# Sensor_Board.net
KiCad netlist of a schematic drawn in EAGLE
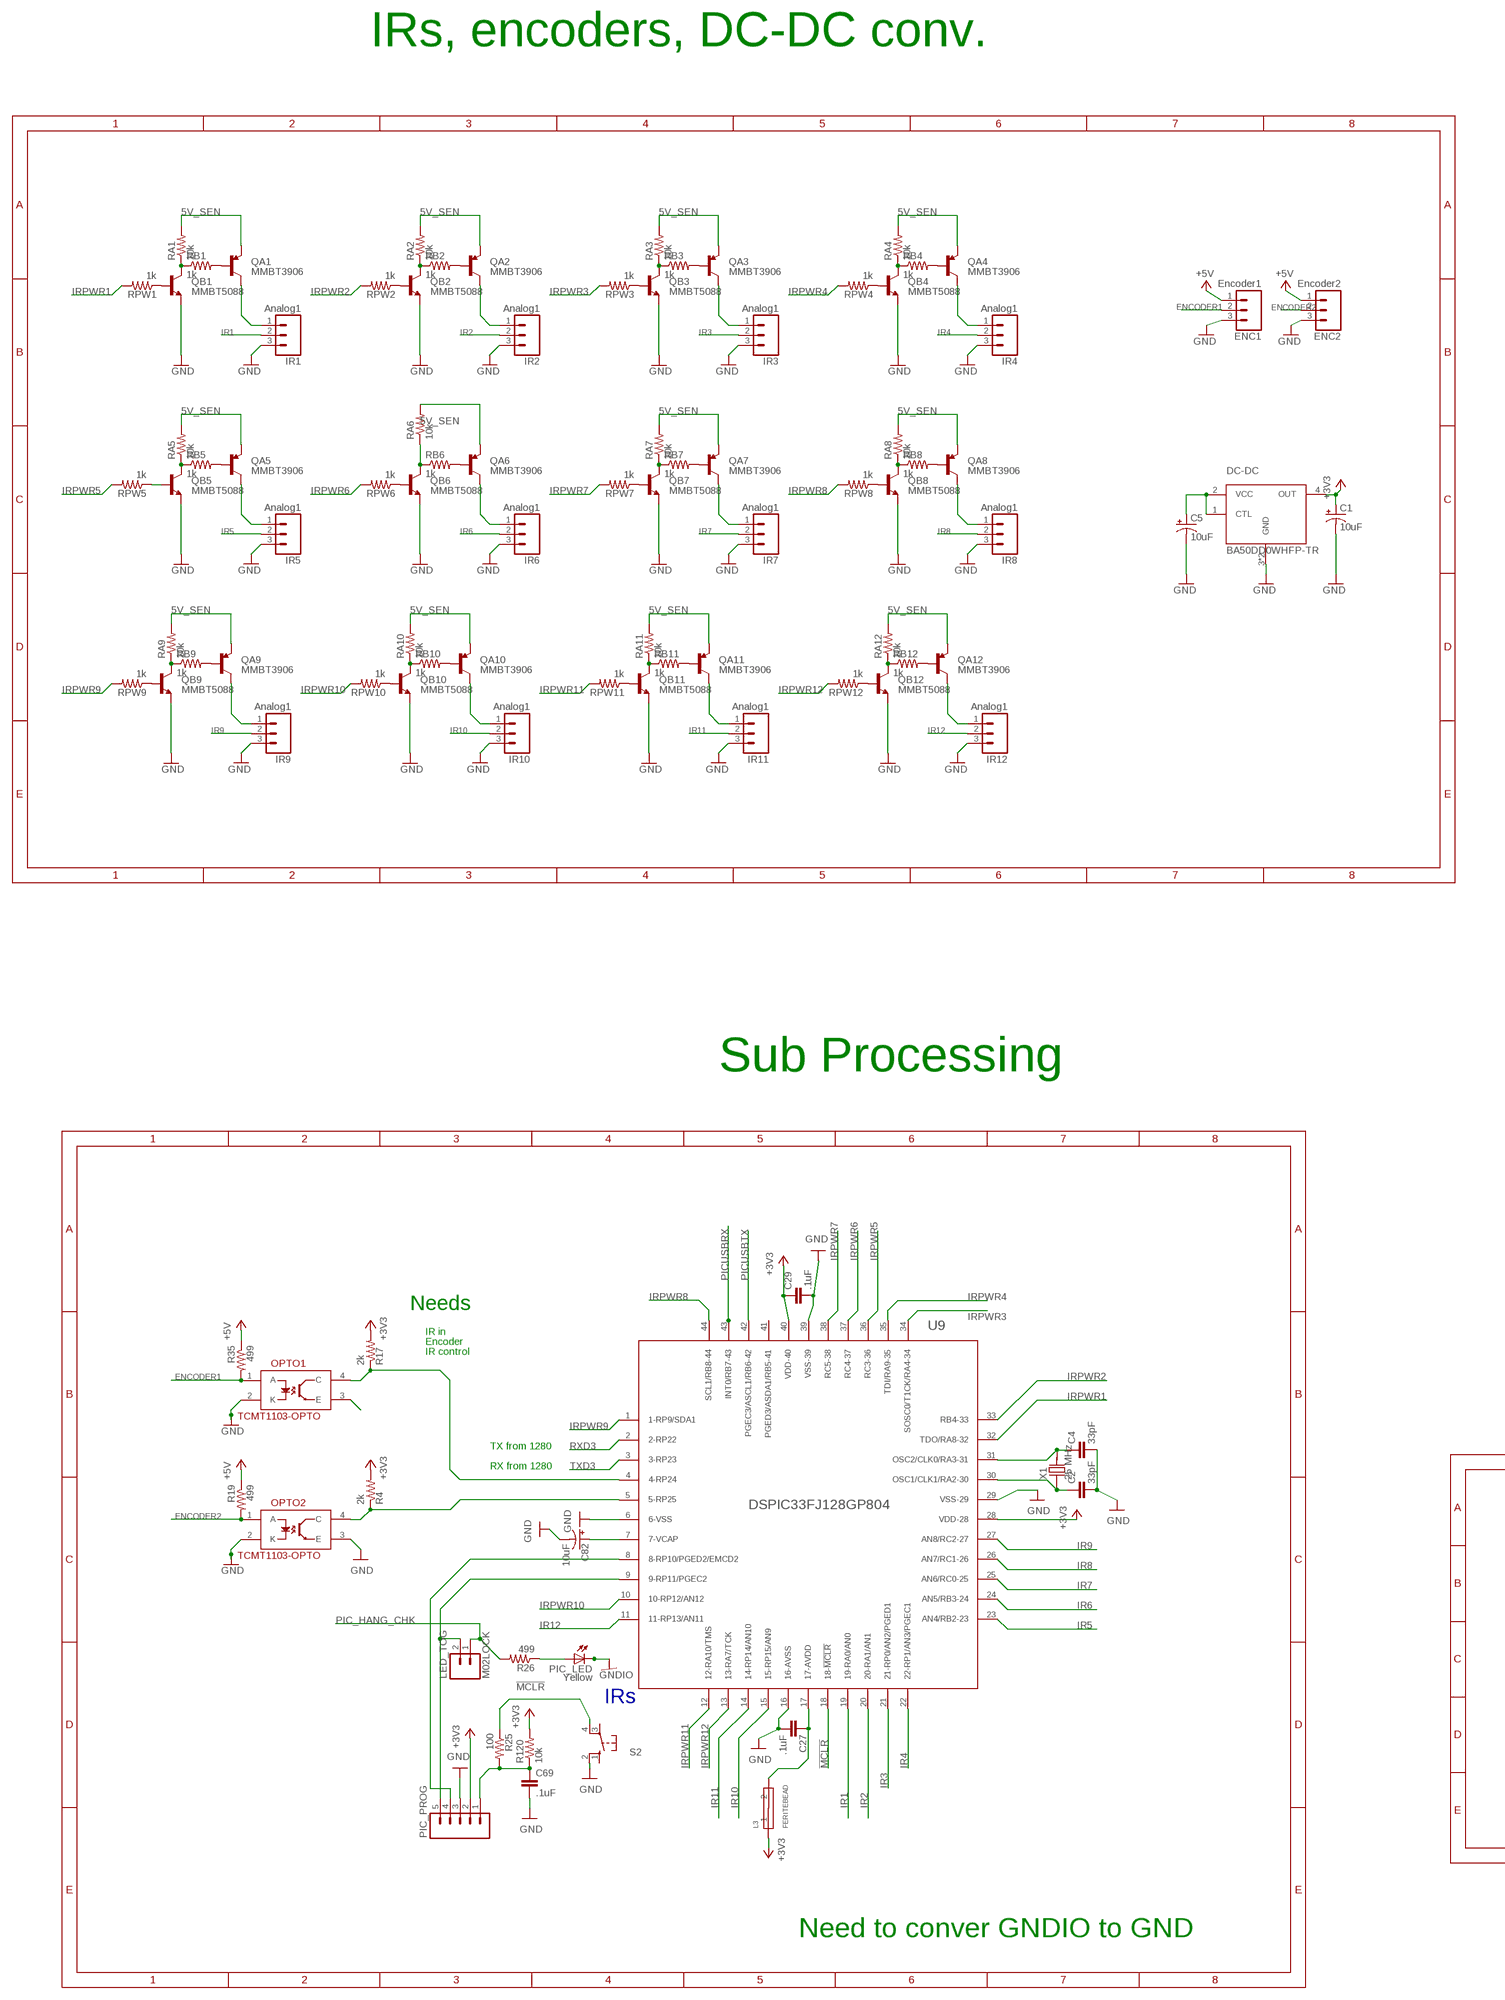
[diagram p0: schematic, sheet 1, part 1 of 3]
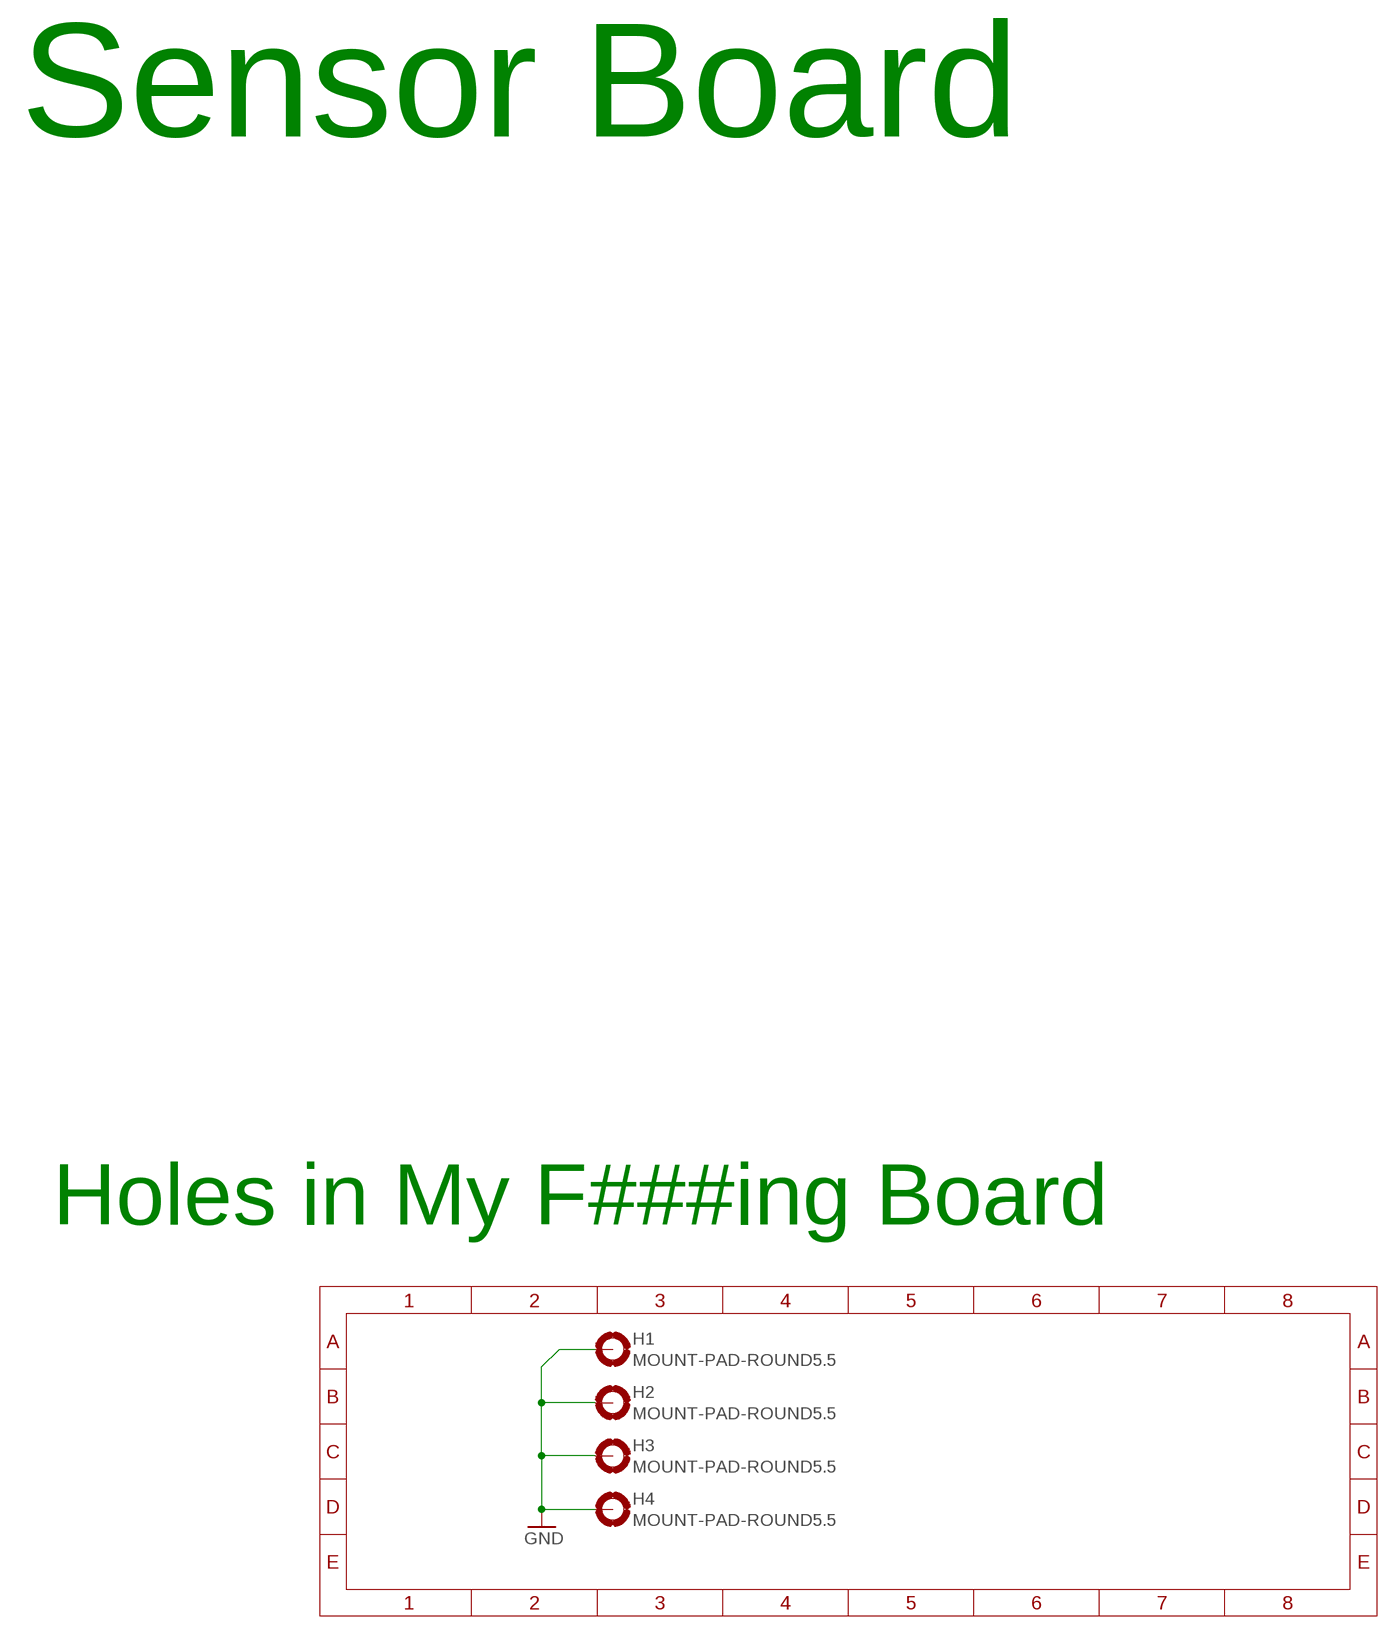
[diagram p1: schematic, sheet 1, part 2 of 3]
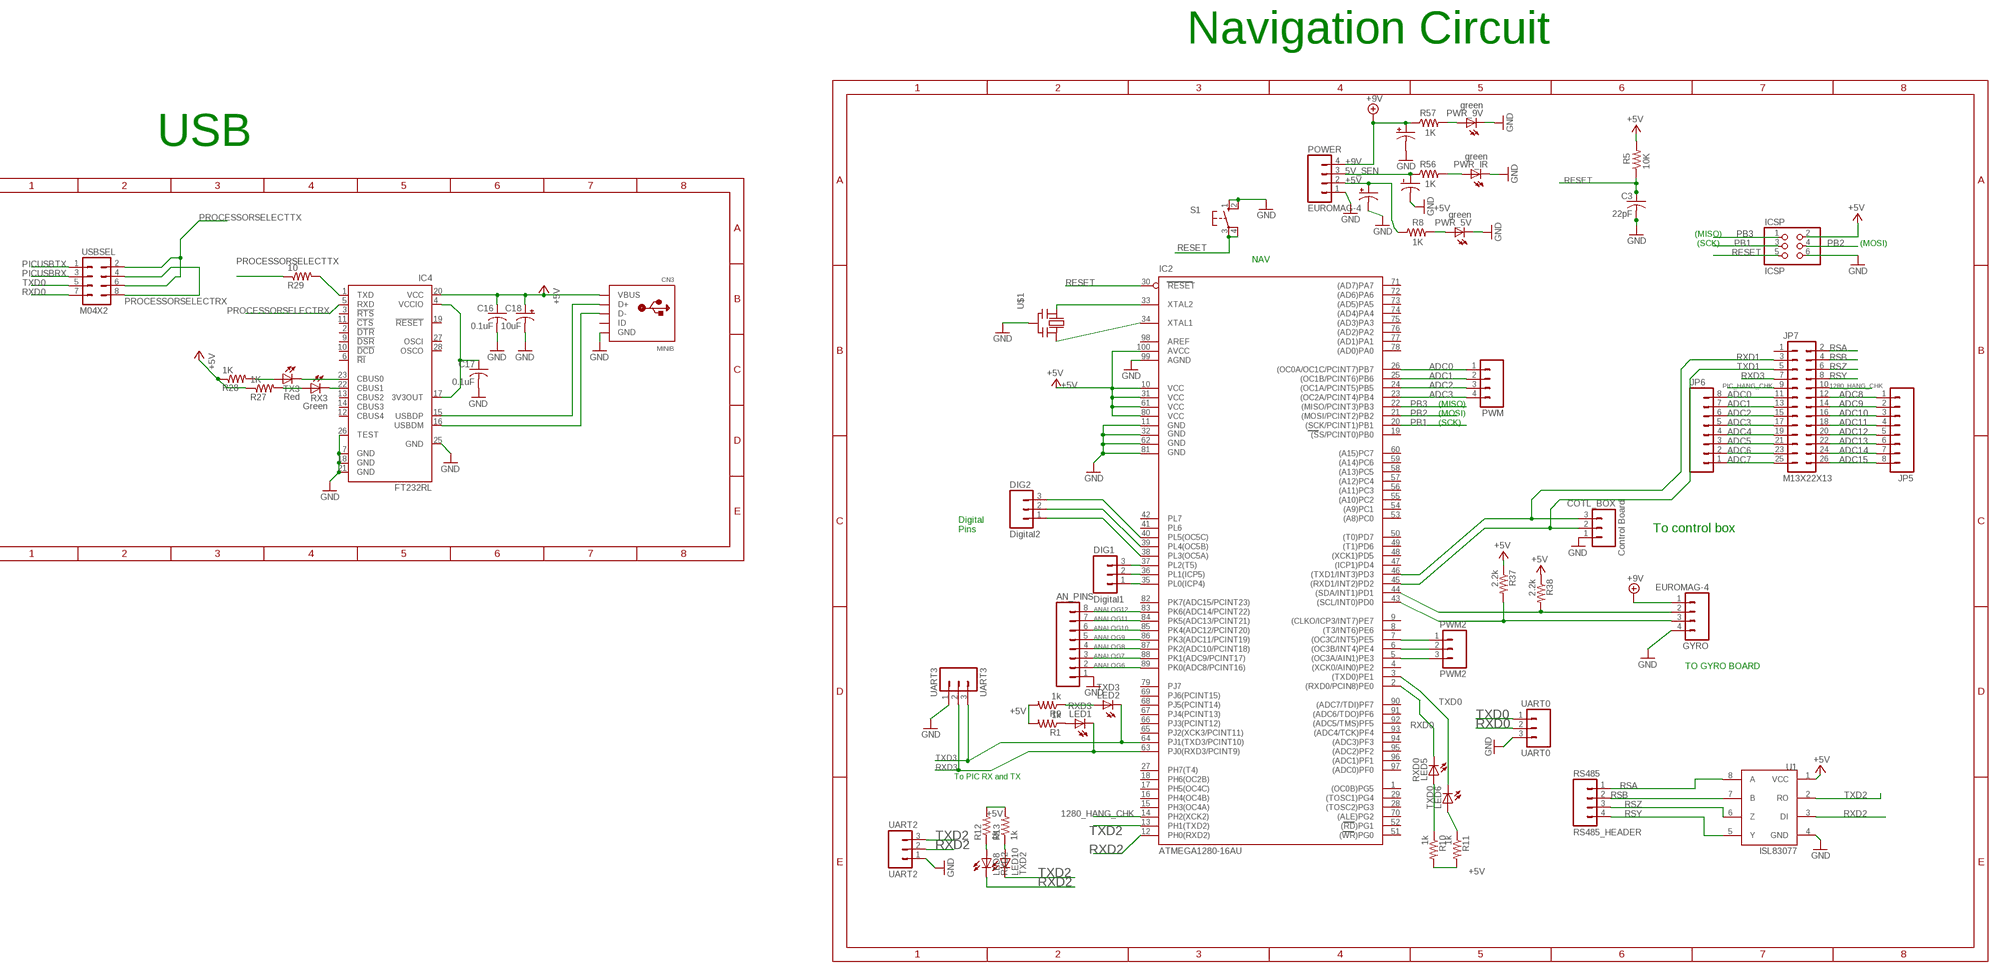
[diagram p2: schematic, sheet 1, part 3 of 3]

(export (version "E")
  (design (tool "Eeschema 10.0.6"))
  (components
    (comp (ref "AN_PINS")
      (value "M08LOCK_LONGPADS")
      (footprint "eagle-import:1X08_LOCK_LONGPADS")
      (libsource (lib "eagle-import") (part "M08LOCK_LONGPADS"))
    )
    (comp (ref "C1")
      (value "10uF")
      (footprint "eagle-import:EIA3216")
      (libsource (lib "eagle-import") (part "SparkFun-Capacitors_CAP_POL1206"))
    )
    (comp (ref "C2")
      (value "33pF")
      (footprint "eagle-import:0805")
      (libsource (lib "eagle-import") (part "1UF-25V-10%(0805)"))
    )
    (comp (ref "C3")
      (value "22pF")
      (footprint "eagle-import:C0805K")
      (libsource (lib "eagle-import") (part "C-USC0805K"))
    )
    (comp (ref "C4")
      (value "33pF")
      (footprint "eagle-import:0805")
      (libsource (lib "eagle-import") (part "1UF-25V-10%(0805)"))
    )
    (comp (ref "C5")
      (value "10uF")
      (footprint "eagle-import:EIA3216")
      (libsource (lib "eagle-import") (part "SparkFun-Capacitors_CAP_POL1206"))
    )
    (comp (ref "C16")
      (value "0.1uF")
      (footprint "eagle-import:C0805K")
      (libsource (lib "eagle-import") (part "C-USC0805K"))
    )
    (comp (ref "C17")
      (value "0.1uF")
      (footprint "eagle-import:C0805K")
      (libsource (lib "eagle-import") (part "C-USC0805K"))
    )
    (comp (ref "C18")
      (value "10uF")
      (footprint "eagle-import:EIA3528-KIT")
      (libsource (lib "eagle-import") (part "CAP_POL3528-KIT"))
    )
    (comp (ref "C27")
      (value ".1uF")
      (footprint "eagle-import:0805")
      (libsource (lib "eagle-import") (part "1UF-25V-10%(0805)"))
    )
    (comp (ref "C29")
      (value ".1uF")
      (footprint "eagle-import:0805")
      (libsource (lib "eagle-import") (part "1UF-25V-10%(0805)"))
    )
    (comp (ref "C69")
      (value ".1uF")
      (footprint "eagle-import:0805")
      (libsource (lib "eagle-import") (part "1UF-25V-10%(0805)"))
    )
    (comp (ref "C82")
      (value "10uF")
      (footprint "eagle-import:POLC1206")
      (libsource (lib "eagle-import") (part "POLCAP"))
    )
    (comp (ref "CAN1")
      (value "EMVY160ADA101MF55G")
      (footprint "eagle-import:140CLH-1010")
      (libsource (lib "eagle-import") (part "CPOL-US140CLH-1010"))
    )
    (comp (ref "CAN2")
      (value "EMVY160ADA101MF55G")
      (footprint "eagle-import:140CLH-1010")
      (libsource (lib "eagle-import") (part "CPOL-US140CLH-1010"))
    )
    (comp (ref "CAN3")
      (value "EMVY160ADA101MF55G")
      (footprint "eagle-import:140CLH-1010")
      (libsource (lib "eagle-import") (part "CPOL-US140CLH-1010"))
    )
    (comp (ref "CN3")
      (value "MINIB")
      (footprint "eagle-import:USB-MINIB")
      (libsource (lib "eagle-import") (part "USBMINIB"))
    )
    (comp (ref "COTL_BOX")
      (value "Control Board")
      (footprint "eagle-import:MOLEX-1X3_LOCK")
      (libsource (lib "eagle-import") (part "M03POLAR_LOCK"))
    )
    (comp (ref "DC-DC")
      (value "BA50DD0WHFP-TR")
      (footprint "eagle-import:HRP5")
      (libsource (lib "eagle-import") (part "BA50DD0WHFP-TR"))
    )
    (comp (ref "DIG1")
      (value "Digital1")
      (footprint "eagle-import:M3")
      (libsource (lib "eagle-import") (part "EUROMAG-390DEG"))
    )
    (comp (ref "DIG2")
      (value "Digital2")
      (footprint "eagle-import:M3")
      (libsource (lib "eagle-import") (part "EUROMAG-390DEG"))
    )
    (comp (ref "ENC1")
      (value "Encoder1")
      (footprint "eagle-import:M3")
      (libsource (lib "eagle-import") (part "EUROMAG-390DEG"))
    )
    (comp (ref "ENC2")
      (value "Encoder2")
      (footprint "eagle-import:M3")
      (libsource (lib "eagle-import") (part "EUROMAG-390DEG"))
    )
    (comp (ref "GYRO")
      (value "EUROMAG-4")
      (footprint "eagle-import:M4")
      (libsource (lib "eagle-import") (part "EUROMAG-4"))
    )
    (comp (ref "H1")
      (value "MOUNT-PAD-ROUND5.5")
      (footprint "eagle-import:5,5-PAD")
      (libsource (lib "eagle-import") (part "MOUNT-PAD-ROUND5.5"))
    )
    (comp (ref "H2")
      (value "MOUNT-PAD-ROUND5.5")
      (footprint "eagle-import:5,5-PAD")
      (libsource (lib "eagle-import") (part "MOUNT-PAD-ROUND5.5"))
    )
    (comp (ref "H3")
      (value "MOUNT-PAD-ROUND5.5")
      (footprint "eagle-import:5,5-PAD")
      (libsource (lib "eagle-import") (part "MOUNT-PAD-ROUND5.5"))
    )
    (comp (ref "H4")
      (value "MOUNT-PAD-ROUND5.5")
      (footprint "eagle-import:5,5-PAD")
      (libsource (lib "eagle-import") (part "MOUNT-PAD-ROUND5.5"))
    )
    (comp (ref "IC2")
      (value "ATMEGA1280-16AU")
      (footprint "eagle-import:TQFP100")
      (libsource (lib "eagle-import") (part "ATMEGAAU1280-16"))
    )
    (comp (ref "IC4")
      (value "FT232RL")
      (footprint "eagle-import:SSOP28")
      (libsource (lib "eagle-import") (part "FT232RL"))
    )
    (comp (ref "ICSP")
      (value "ICSP")
      (footprint "eagle-import:2X03")
      (libsource (lib "eagle-import") (part "PINHD-2X3"))
    )
    (comp (ref "IR1")
      (value "Analog1")
      (footprint "eagle-import:M3")
      (libsource (lib "eagle-import") (part "EUROMAG-390DEG"))
    )
    (comp (ref "IR2")
      (value "Analog1")
      (footprint "eagle-import:M3")
      (libsource (lib "eagle-import") (part "EUROMAG-390DEG"))
    )
    (comp (ref "IR3")
      (value "Analog1")
      (footprint "eagle-import:M3")
      (libsource (lib "eagle-import") (part "EUROMAG-390DEG"))
    )
    (comp (ref "IR4")
      (value "Analog1")
      (footprint "eagle-import:M3")
      (libsource (lib "eagle-import") (part "EUROMAG-390DEG"))
    )
    (comp (ref "IR5")
      (value "Analog1")
      (footprint "eagle-import:M3")
      (libsource (lib "eagle-import") (part "EUROMAG-390DEG"))
    )
    (comp (ref "IR6")
      (value "Analog1")
      (footprint "eagle-import:M3")
      (libsource (lib "eagle-import") (part "EUROMAG-390DEG"))
    )
    (comp (ref "IR7")
      (value "Analog1")
      (footprint "eagle-import:M3")
      (libsource (lib "eagle-import") (part "EUROMAG-390DEG"))
    )
    (comp (ref "IR8")
      (value "Analog1")
      (footprint "eagle-import:M3")
      (libsource (lib "eagle-import") (part "EUROMAG-390DEG"))
    )
    (comp (ref "IR9")
      (value "Analog1")
      (footprint "eagle-import:M3")
      (libsource (lib "eagle-import") (part "EUROMAG-390DEG"))
    )
    (comp (ref "IR10")
      (value "Analog1")
      (footprint "eagle-import:M3")
      (libsource (lib "eagle-import") (part "EUROMAG-390DEG"))
    )
    (comp (ref "IR11")
      (value "Analog1")
      (footprint "eagle-import:M3")
      (libsource (lib "eagle-import") (part "EUROMAG-390DEG"))
    )
    (comp (ref "IR12")
      (value "Analog1")
      (footprint "eagle-import:M3")
      (libsource (lib "eagle-import") (part "EUROMAG-390DEG"))
    )
    (comp (ref "JP5")
      (value "M08LOCK_LONGPADS")
      (footprint "eagle-import:1X08_LOCK_LONGPADS")
      (libsource (lib "eagle-import") (part "M08LOCK_LONGPADS"))
    )
    (comp (ref "JP6")
      (value "M08LOCK_LONGPADS")
      (footprint "eagle-import:1X08_LOCK_LONGPADS")
      (libsource (lib "eagle-import") (part "M08LOCK_LONGPADS"))
    )
    (comp (ref "JP7")
      (value "M13X22X13")
      (footprint "eagle-import:2X13")
      (libsource (lib "eagle-import") (part "M13X22X13"))
    )
    (comp (ref "L3")
      (value "FERITEBEAD")
      (footprint "eagle-import:0603")
      (libsource (lib "eagle-import") (part "FERITEBEAD"))
    )
    (comp (ref "LED1")
      (value "RXD3")
      (footprint "eagle-import:CHIP-LED0805")
      (libsource (lib "eagle-import") (part "LEDCHIP-LED0805"))
    )
    (comp (ref "LED2")
      (value "TXD3")
      (footprint "eagle-import:CHIP-LED0805")
      (libsource (lib "eagle-import") (part "LEDCHIP-LED0805"))
    )
    (comp (ref "LED5")
      (value "RXD0")
      (footprint "eagle-import:CHIP-LED0805")
      (libsource (lib "eagle-import") (part "LEDCHIP-LED0805"))
    )
    (comp (ref "LED6")
      (value "TXD0")
      (footprint "eagle-import:CHIP-LED0805")
      (libsource (lib "eagle-import") (part "LEDCHIP-LED0805"))
    )
    (comp (ref "LED8")
      (value "RXD2")
      (footprint "eagle-import:CHIP-LED0805")
      (libsource (lib "eagle-import") (part "LEDCHIP-LED0805"))
    )
    (comp (ref "LED10")
      (value "TXD2")
      (footprint "eagle-import:CHIP-LED0805")
      (libsource (lib "eagle-import") (part "LEDCHIP-LED0805"))
    )
    (comp (ref "LED_TOG")
      (value "M02LOCK")
      (footprint "eagle-import:1X02_LOCK")
      (libsource (lib "eagle-import") (part "M02LOCK"))
    )
    (comp (ref "OPTO1")
      (value "TCMT1103-OPTO")
      (footprint "eagle-import:SSOP-4")
      (libsource (lib "eagle-import") (part "TCMT1103-OPTO"))
    )
    (comp (ref "OPTO2")
      (value "TCMT1103-OPTO")
      (footprint "eagle-import:SSOP-4")
      (libsource (lib "eagle-import") (part "TCMT1103-OPTO"))
    )
    (comp (ref "PIC_LED")
      (value "Yellow")
      (footprint "eagle-import:CHIP-LED0805")
      (libsource (lib "eagle-import") (part "LEDCHIP-LED0805"))
    )
    (comp (ref "PIC_PROG")
      (value "M05LOCK_LONGPADS")
      (footprint "eagle-import:1X05_LOCK_LONGPADS")
      (libsource (lib "eagle-import") (part "M05LOCK_LONGPADS"))
    )
    (comp (ref "POWER")
      (value "EUROMAG-4")
      (footprint "eagle-import:M4")
      (libsource (lib "eagle-import") (part "EUROMAG-4"))
    )
    (comp (ref "PWM")
      (value "M04POLAR")
      (footprint "eagle-import:MOLEX-1X4")
      (libsource (lib "eagle-import") (part "M04POLAR"))
    )
    (comp (ref "PWM2")
      (value "PWM2")
      (footprint "eagle-import:MOLEX-1X3_LOCK")
      (libsource (lib "eagle-import") (part "M03POLAR_LOCK"))
    )
    (comp (ref "PWR_5V")
      (value "green")
      (footprint "eagle-import:CHIPLED_0805")
      (libsource (lib "eagle-import") (part "LEDCHIPLED_0805"))
    )
    (comp (ref "PWR_9V")
      (value "green")
      (footprint "eagle-import:CHIPLED_0805")
      (libsource (lib "eagle-import") (part "LEDCHIPLED_0805"))
    )
    (comp (ref "PWR_IR")
      (value "green")
      (footprint "eagle-import:CHIPLED_0805")
      (libsource (lib "eagle-import") (part "LEDCHIPLED_0805"))
    )
    (comp (ref "QA1")
      (value "MMBT3906")
      (footprint "eagle-import:SOT23")
      (libsource (lib "eagle-import") (part "TRANSISTOR_PNPMMBT3906"))
    )
    (comp (ref "QA2")
      (value "MMBT3906")
      (footprint "eagle-import:SOT23")
      (libsource (lib "eagle-import") (part "TRANSISTOR_PNPMMBT3906"))
    )
    (comp (ref "QA3")
      (value "MMBT3906")
      (footprint "eagle-import:SOT23")
      (libsource (lib "eagle-import") (part "TRANSISTOR_PNPMMBT3906"))
    )
    (comp (ref "QA4")
      (value "MMBT3906")
      (footprint "eagle-import:SOT23")
      (libsource (lib "eagle-import") (part "TRANSISTOR_PNPMMBT3906"))
    )
    (comp (ref "QA5")
      (value "MMBT3906")
      (footprint "eagle-import:SOT23")
      (libsource (lib "eagle-import") (part "TRANSISTOR_PNPMMBT3906"))
    )
    (comp (ref "QA6")
      (value "MMBT3906")
      (footprint "eagle-import:SOT23")
      (libsource (lib "eagle-import") (part "TRANSISTOR_PNPMMBT3906"))
    )
    (comp (ref "QA7")
      (value "MMBT3906")
      (footprint "eagle-import:SOT23")
      (libsource (lib "eagle-import") (part "TRANSISTOR_PNPMMBT3906"))
    )
    (comp (ref "QA8")
      (value "MMBT3906")
      (footprint "eagle-import:SOT23")
      (libsource (lib "eagle-import") (part "TRANSISTOR_PNPMMBT3906"))
    )
    (comp (ref "QA9")
      (value "MMBT3906")
      (footprint "eagle-import:SOT23")
      (libsource (lib "eagle-import") (part "TRANSISTOR_PNPMMBT3906"))
    )
    (comp (ref "QA10")
      (value "MMBT3906")
      (footprint "eagle-import:SOT23")
      (libsource (lib "eagle-import") (part "TRANSISTOR_PNPMMBT3906"))
    )
    (comp (ref "QA11")
      (value "MMBT3906")
      (footprint "eagle-import:SOT23")
      (libsource (lib "eagle-import") (part "TRANSISTOR_PNPMMBT3906"))
    )
    (comp (ref "QA12")
      (value "MMBT3906")
      (footprint "eagle-import:SOT23")
      (libsource (lib "eagle-import") (part "TRANSISTOR_PNPMMBT3906"))
    )
    (comp (ref "QB1")
      (value "MMBT5088")
      (footprint "eagle-import:SOT23")
      (libsource (lib "eagle-import") (part "TRANSISTOR_NPNMMBT5088"))
    )
    (comp (ref "QB2")
      (value "MMBT5088")
      (footprint "eagle-import:SOT23")
      (libsource (lib "eagle-import") (part "TRANSISTOR_NPNMMBT5088"))
    )
    (comp (ref "QB3")
      (value "MMBT5088")
      (footprint "eagle-import:SOT23")
      (libsource (lib "eagle-import") (part "TRANSISTOR_NPNMMBT5088"))
    )
    (comp (ref "QB4")
      (value "MMBT5088")
      (footprint "eagle-import:SOT23")
      (libsource (lib "eagle-import") (part "TRANSISTOR_NPNMMBT5088"))
    )
    (comp (ref "QB5")
      (value "MMBT5088")
      (footprint "eagle-import:SOT23")
      (libsource (lib "eagle-import") (part "TRANSISTOR_NPNMMBT5088"))
    )
    (comp (ref "QB6")
      (value "MMBT5088")
      (footprint "eagle-import:SOT23")
      (libsource (lib "eagle-import") (part "TRANSISTOR_NPNMMBT5088"))
    )
    (comp (ref "QB7")
      (value "MMBT5088")
      (footprint "eagle-import:SOT23")
      (libsource (lib "eagle-import") (part "TRANSISTOR_NPNMMBT5088"))
    )
    (comp (ref "QB8")
      (value "MMBT5088")
      (footprint "eagle-import:SOT23")
      (libsource (lib "eagle-import") (part "TRANSISTOR_NPNMMBT5088"))
    )
    (comp (ref "QB9")
      (value "MMBT5088")
      (footprint "eagle-import:SOT23")
      (libsource (lib "eagle-import") (part "TRANSISTOR_NPNMMBT5088"))
    )
    (comp (ref "QB10")
      (value "MMBT5088")
      (footprint "eagle-import:SOT23")
      (libsource (lib "eagle-import") (part "TRANSISTOR_NPNMMBT5088"))
    )
    (comp (ref "QB11")
      (value "MMBT5088")
      (footprint "eagle-import:SOT23")
      (libsource (lib "eagle-import") (part "TRANSISTOR_NPNMMBT5088"))
    )
    (comp (ref "QB12")
      (value "MMBT5088")
      (footprint "eagle-import:SOT23")
      (libsource (lib "eagle-import") (part "TRANSISTOR_NPNMMBT5088"))
    )
    (comp (ref "R1")
      (value "1k")
      (footprint "eagle-import:R0805")
      (libsource (lib "eagle-import") (part "adafruit_R-US_R0805"))
    )
    (comp (ref "R4")
      (value "2k")
      (footprint "eagle-import:R0805")
      (libsource (lib "eagle-import") (part "adafruit_R-US_R0805"))
    )
    (comp (ref "R5")
      (value "10K")
      (footprint "eagle-import:R0805")
      (libsource (lib "eagle-import") (part "R-US_R0805"))
    )
    (comp (ref "R8")
      (value "1K")
      (footprint "eagle-import:R0805")
      (libsource (lib "eagle-import") (part "R-US_R0805"))
    )
    (comp (ref "R9")
      (value "1k")
      (footprint "eagle-import:R0805")
      (libsource (lib "eagle-import") (part "adafruit_R-US_R0805"))
    )
    (comp (ref "R10")
      (value "1k")
      (footprint "eagle-import:R0805")
      (libsource (lib "eagle-import") (part "adafruit_R-US_R0805"))
    )
    (comp (ref "R11")
      (value "1k")
      (footprint "eagle-import:R0805")
      (libsource (lib "eagle-import") (part "adafruit_R-US_R0805"))
    )
    (comp (ref "R12")
      (value "1k")
      (footprint "eagle-import:R0805")
      (libsource (lib "eagle-import") (part "adafruit_R-US_R0805"))
    )
    (comp (ref "R13")
      (value "1k")
      (footprint "eagle-import:R0805")
      (libsource (lib "eagle-import") (part "adafruit_R-US_R0805"))
    )
    (comp (ref "R17")
      (value "2k")
      (footprint "eagle-import:R0805")
      (libsource (lib "eagle-import") (part "adafruit_R-US_R0805"))
    )
    (comp (ref "R19")
      (value "499")
      (footprint "eagle-import:R0805")
      (libsource (lib "eagle-import") (part "adafruit_R-US_R0805"))
    )
    (comp (ref "R25")
      (value "100")
      (footprint "eagle-import:R0805")
      (libsource (lib "eagle-import") (part "adafruit_R-US_R0805"))
    )
    (comp (ref "R26")
      (value "499")
      (footprint "eagle-import:R0805")
      (libsource (lib "eagle-import") (part "adafruit_R-US_R0805"))
    )
    (comp (ref "R27")
      (value "1K")
      (footprint "eagle-import:R0805")
      (libsource (lib "eagle-import") (part "adafruit_R-US_R0805"))
    )
    (comp (ref "R28")
      (value "1K")
      (footprint "eagle-import:R0805")
      (libsource (lib "eagle-import") (part "adafruit_R-US_R0805"))
    )
    (comp (ref "R29")
      (value "10")
      (footprint "eagle-import:R0805")
      (libsource (lib "eagle-import") (part "adafruit_R-US_R0805"))
    )
    (comp (ref "R35")
      (value "499")
      (footprint "eagle-import:R0805")
      (libsource (lib "eagle-import") (part "adafruit_R-US_R0805"))
    )
    (comp (ref "R37")
      (value "2.2k")
      (footprint "eagle-import:R0805")
      (libsource (lib "eagle-import") (part "adafruit_R-US_R0805"))
    )
    (comp (ref "R38")
      (value "2.2k")
      (footprint "eagle-import:R0805")
      (libsource (lib "eagle-import") (part "adafruit_R-US_R0805"))
    )
    (comp (ref "R56")
      (value "1K")
      (footprint "eagle-import:R0805")
      (libsource (lib "eagle-import") (part "R-US_R0805"))
    )
    (comp (ref "R57")
      (value "1K")
      (footprint "eagle-import:R0805")
      (libsource (lib "eagle-import") (part "R-US_R0805"))
    )
    (comp (ref "R120")
      (value "10k")
      (footprint "eagle-import:R0805")
      (libsource (lib "eagle-import") (part "adafruit_R-US_R0805"))
    )
    (comp (ref "RA1")
      (value "10k")
      (footprint "eagle-import:0805")
      (libsource (lib "eagle-import") (part "RESISTOR0805-RES"))
    )
    (comp (ref "RA2")
      (value "10k")
      (footprint "eagle-import:0805")
      (libsource (lib "eagle-import") (part "RESISTOR0805-RES"))
    )
    (comp (ref "RA3")
      (value "10k")
      (footprint "eagle-import:0805")
      (libsource (lib "eagle-import") (part "RESISTOR0805-RES"))
    )
    (comp (ref "RA4")
      (value "10k")
      (footprint "eagle-import:0805")
      (libsource (lib "eagle-import") (part "RESISTOR0805-RES"))
    )
    (comp (ref "RA5")
      (value "10k")
      (footprint "eagle-import:0805")
      (libsource (lib "eagle-import") (part "RESISTOR0805-RES"))
    )
    (comp (ref "RA6")
      (value "10k")
      (footprint "eagle-import:0805")
      (libsource (lib "eagle-import") (part "RESISTOR0805-RES"))
    )
    (comp (ref "RA7")
      (value "10k")
      (footprint "eagle-import:0805")
      (libsource (lib "eagle-import") (part "RESISTOR0805-RES"))
    )
    (comp (ref "RA8")
      (value "10k")
      (footprint "eagle-import:0805")
      (libsource (lib "eagle-import") (part "RESISTOR0805-RES"))
    )
    (comp (ref "RA9")
      (value "10k")
      (footprint "eagle-import:0805")
      (libsource (lib "eagle-import") (part "RESISTOR0805-RES"))
    )
    (comp (ref "RA10")
      (value "10k")
      (footprint "eagle-import:0805")
      (libsource (lib "eagle-import") (part "RESISTOR0805-RES"))
    )
    (comp (ref "RA11")
      (value "10k")
      (footprint "eagle-import:0805")
      (libsource (lib "eagle-import") (part "RESISTOR0805-RES"))
    )
    (comp (ref "RA12")
      (value "10k")
      (footprint "eagle-import:0805")
      (libsource (lib "eagle-import") (part "RESISTOR0805-RES"))
    )
    (comp (ref "RB1")
      (value "1k")
      (footprint "eagle-import:0805")
      (libsource (lib "eagle-import") (part "RESISTOR0805-RES"))
    )
    (comp (ref "RB2")
      (value "1k")
      (footprint "eagle-import:0805")
      (libsource (lib "eagle-import") (part "RESISTOR0805-RES"))
    )
    (comp (ref "RB3")
      (value "1k")
      (footprint "eagle-import:0805")
      (libsource (lib "eagle-import") (part "RESISTOR0805-RES"))
    )
    (comp (ref "RB4")
      (value "1k")
      (footprint "eagle-import:0805")
      (libsource (lib "eagle-import") (part "RESISTOR0805-RES"))
    )
    (comp (ref "RB5")
      (value "1k")
      (footprint "eagle-import:0805")
      (libsource (lib "eagle-import") (part "RESISTOR0805-RES"))
    )
    (comp (ref "RB6")
      (value "1k")
      (footprint "eagle-import:0805")
      (libsource (lib "eagle-import") (part "RESISTOR0805-RES"))
    )
    (comp (ref "RB7")
      (value "1k")
      (footprint "eagle-import:0805")
      (libsource (lib "eagle-import") (part "RESISTOR0805-RES"))
    )
    (comp (ref "RB8")
      (value "1k")
      (footprint "eagle-import:0805")
      (libsource (lib "eagle-import") (part "RESISTOR0805-RES"))
    )
    (comp (ref "RB9")
      (value "1k")
      (footprint "eagle-import:0805")
      (libsource (lib "eagle-import") (part "RESISTOR0805-RES"))
    )
    (comp (ref "RB10")
      (value "1k")
      (footprint "eagle-import:0805")
      (libsource (lib "eagle-import") (part "RESISTOR0805-RES"))
    )
    (comp (ref "RB11")
      (value "1k")
      (footprint "eagle-import:0805")
      (libsource (lib "eagle-import") (part "RESISTOR0805-RES"))
    )
    (comp (ref "RB12")
      (value "1k")
      (footprint "eagle-import:0805")
      (libsource (lib "eagle-import") (part "RESISTOR0805-RES"))
    )
    (comp (ref "RPW1")
      (value "1k")
      (footprint "eagle-import:0805")
      (libsource (lib "eagle-import") (part "RESISTOR0805-RES"))
    )
    (comp (ref "RPW2")
      (value "1k")
      (footprint "eagle-import:0805")
      (libsource (lib "eagle-import") (part "RESISTOR0805-RES"))
    )
    (comp (ref "RPW3")
      (value "1k")
      (footprint "eagle-import:0805")
      (libsource (lib "eagle-import") (part "RESISTOR0805-RES"))
    )
    (comp (ref "RPW4")
      (value "1k")
      (footprint "eagle-import:0805")
      (libsource (lib "eagle-import") (part "RESISTOR0805-RES"))
    )
    (comp (ref "RPW5")
      (value "1k")
      (footprint "eagle-import:0805")
      (libsource (lib "eagle-import") (part "RESISTOR0805-RES"))
    )
    (comp (ref "RPW6")
      (value "1k")
      (footprint "eagle-import:0805")
      (libsource (lib "eagle-import") (part "RESISTOR0805-RES"))
    )
    (comp (ref "RPW7")
      (value "1k")
      (footprint "eagle-import:0805")
      (libsource (lib "eagle-import") (part "RESISTOR0805-RES"))
    )
    (comp (ref "RPW8")
      (value "1k")
      (footprint "eagle-import:0805")
      (libsource (lib "eagle-import") (part "RESISTOR0805-RES"))
    )
    (comp (ref "RPW9")
      (value "1k")
      (footprint "eagle-import:0805")
      (libsource (lib "eagle-import") (part "RESISTOR0805-RES"))
    )
    (comp (ref "RPW10")
      (value "1k")
      (footprint "eagle-import:0805")
      (libsource (lib "eagle-import") (part "RESISTOR0805-RES"))
    )
    (comp (ref "RPW11")
      (value "1k")
      (footprint "eagle-import:0805")
      (libsource (lib "eagle-import") (part "RESISTOR0805-RES"))
    )
    (comp (ref "RPW12")
      (value "1k")
      (footprint "eagle-import:0805")
      (libsource (lib "eagle-import") (part "RESISTOR0805-RES"))
    )
    (comp (ref "RS485_HEADER")
      (value "RS485")
      (footprint "eagle-import:M4-90")
      (libsource (lib "eagle-import") (part "EUROMAG-4UP"))
    )
    (comp (ref "RX3")
      (value "Green")
      (footprint "eagle-import:CHIP-LED0805")
      (libsource (lib "eagle-import") (part "LEDCHIP-LED0805"))
    )
    (comp (ref "S1")
      (value "10-XX")
      (footprint "eagle-import:B3F-10XX")
      (libsource (lib "eagle-import") (part "10-XX"))
    )
    (comp (ref "S2")
      (value "10-XX")
      (footprint "eagle-import:B3F-10XX")
      (libsource (lib "eagle-import") (part "10-XX"))
    )
    (comp (ref "TX3")
      (value "Red")
      (footprint "eagle-import:CHIP-LED0805")
      (libsource (lib "eagle-import") (part "LEDCHIP-LED0805"))
    )
    (comp (ref "U$1")
      (value "CERMOSCILL-AWCSR")
      (footprint "eagle-import:AWCSR")
      (libsource (lib "eagle-import") (part "CERMOSCILL-AWCSR"))
    )
    (comp (ref "U1")
      (value "ISL83077")
      (footprint "eagle-import:SO08")
      (libsource (lib "eagle-import") (part "ISL83077"))
    )
    (comp (ref "U9")
      (value "DSPIC33FJ128GP804")
      (footprint "eagle-import:TQFP-44")
      (libsource (lib "eagle-import") (part "DSPIC33FJ128GP204"))
    )
    (comp (ref "UART0")
      (value "UART0")
      (footprint "eagle-import:1X03")
      (libsource (lib "eagle-import") (part "M03PTH"))
    )
    (comp (ref "UART2")
      (value "UART2")
      (footprint "eagle-import:1X03")
      (libsource (lib "eagle-import") (part "M03PTH"))
    )
    (comp (ref "UART3")
      (value "UART3")
      (footprint "eagle-import:1X03")
      (libsource (lib "eagle-import") (part "M03PTH"))
    )
    (comp (ref "USBSEL")
      (value "M04X2")
      (footprint "eagle-import:2X4")
      (libsource (lib "eagle-import") (part "M04X2"))
    )
    (comp (ref "X1")
      (value "25 MHz")
      (footprint "eagle-import:XRCGB-CYL")
      (libsource (lib "eagle-import") (part "XRCGBCRYSTAL"))
    )
  )
  (nets
    (net (code "1") (name "+3V3") (class "Default")
      (node (ref "C1") (pin "A") (pinfunction "+_A") (pintype "passive"))
      (node (ref "C29") (pin "1") (pinfunction "1_1") (pintype "passive"))
      (node (ref "DC-DC") (pin "4") (pinfunction "OUT_4") (pintype "bidirectional"))
      (node (ref "L3") (pin "1") (pinfunction "P$1_1") (pintype "bidirectional"))
      (node (ref "PIC_PROG") (pin "2") (pinfunction "2_2") (pintype "passive"))
      (node (ref "R120") (pin "2") (pinfunction "2_2") (pintype "passive"))
      (node (ref "R17") (pin "2") (pinfunction "2_2") (pintype "passive"))
      (node (ref "R4") (pin "2") (pinfunction "2_2") (pintype "passive"))
      (node (ref "U9") (pin "28") (pinfunction "VDD-28_28") (pintype "bidirectional"))
      (node (ref "U9") (pin "40") (pinfunction "VDD-40_40") (pintype "bidirectional"))
    )
    (net (code "2") (name "+5V") (class "Default")
      (node (ref "C16") (pin "1") (pinfunction "1_1") (pintype "passive"))
      (node (ref "C18") (pin "A") (pinfunction "+_A") (pintype "passive"))
      (node (ref "C5") (pin "A") (pinfunction "+_A") (pintype "passive"))
      (node (ref "CAN3") (pin "+") (pinfunction "+_+") (pintype "passive"))
      (node (ref "CN3") (pin "VBUS") (pinfunction "VBUS_VBUS") (pintype "power_in"))
      (node (ref "DC-DC") (pin "1") (pinfunction "CTL_1") (pintype "bidirectional"))
      (node (ref "DC-DC") (pin "2") (pinfunction "VCC_2") (pintype "bidirectional"))
      (node (ref "ENC1") (pin "1") (pinfunction "1_1") (pintype "passive"))
      (node (ref "ENC2") (pin "1") (pinfunction "1_1") (pintype "passive"))
      (node (ref "IC2") (pin "10") (pinfunction "VCC_10") (pintype "power_in"))
      (node (ref "IC2") (pin "100") (pinfunction "AVCC_100") (pintype "power_in"))
      (node (ref "IC2") (pin "31") (pinfunction "VCC1_31") (pintype "power_in"))
      (node (ref "IC2") (pin "61") (pinfunction "VCC2_61") (pintype "power_in"))
      (node (ref "IC2") (pin "80") (pinfunction "VCC3_80") (pintype "power_in"))
      (node (ref "IC4") (pin "20") (pinfunction "VCC_20") (pintype "input"))
      (node (ref "ICSP") (pin "2") (pinfunction "2_2") (pintype "passive"))
      (node (ref "POWER") (pin "2") (pinfunction "2_2") (pintype "passive"))
      (node (ref "R1") (pin "2") (pinfunction "2_2") (pintype "passive"))
      (node (ref "R10") (pin "2") (pinfunction "2_2") (pintype "passive"))
      (node (ref "R11") (pin "2") (pinfunction "2_2") (pintype "passive"))
      (node (ref "R12") (pin "2") (pinfunction "2_2") (pintype "passive"))
      (node (ref "R13") (pin "2") (pinfunction "2_2") (pintype "passive"))
      (node (ref "R19") (pin "1") (pinfunction "1_1") (pintype "passive"))
      (node (ref "R27") (pin "1") (pinfunction "1_1") (pintype "passive"))
      (node (ref "R28") (pin "1") (pinfunction "1_1") (pintype "passive"))
      (node (ref "R35") (pin "1") (pinfunction "1_1") (pintype "passive"))
      (node (ref "R37") (pin "1") (pinfunction "1_1") (pintype "passive"))
      (node (ref "R38") (pin "1") (pinfunction "1_1") (pintype "passive"))
      (node (ref "R5") (pin "2") (pinfunction "2_2") (pintype "passive"))
      (node (ref "R8") (pin "1") (pinfunction "1_1") (pintype "passive"))
      (node (ref "R9") (pin "2") (pinfunction "2_2") (pintype "passive"))
      (node (ref "U1") (pin "1") (pinfunction "VCC_1") (pintype "bidirectional"))
    )
    (net (code "3") (name "+9V") (class "Default")
      (node (ref "CAN1") (pin "+") (pinfunction "+_+") (pintype "passive"))
      (node (ref "GYRO") (pin "1") (pinfunction "1_1") (pintype "passive"))
      (node (ref "POWER") (pin "4") (pinfunction "4_4") (pintype "passive"))
      (node (ref "R57") (pin "1") (pinfunction "1_1") (pintype "passive"))
    )
    (net (code "4") (name "/5V_SEN") (class "Default")
      (node (ref "CAN2") (pin "+") (pinfunction "+_+") (pintype "passive"))
      (node (ref "POWER") (pin "3") (pinfunction "3_3") (pintype "passive"))
      (node (ref "QA1") (pin "2") (pinfunction "E_2") (pintype "passive"))
      (node (ref "QA10") (pin "2") (pinfunction "E_2") (pintype "passive"))
      (node (ref "QA11") (pin "2") (pinfunction "E_2") (pintype "passive"))
      (node (ref "QA12") (pin "2") (pinfunction "E_2") (pintype "passive"))
      (node (ref "QA2") (pin "2") (pinfunction "E_2") (pintype "passive"))
      (node (ref "QA3") (pin "2") (pinfunction "E_2") (pintype "passive"))
      (node (ref "QA4") (pin "2") (pinfunction "E_2") (pintype "passive"))
      (node (ref "QA5") (pin "2") (pinfunction "E_2") (pintype "passive"))
      (node (ref "QA6") (pin "2") (pinfunction "E_2") (pintype "passive"))
      (node (ref "QA7") (pin "2") (pinfunction "E_2") (pintype "passive"))
      (node (ref "QA8") (pin "2") (pinfunction "E_2") (pintype "passive"))
      (node (ref "QA9") (pin "2") (pinfunction "E_2") (pintype "passive"))
      (node (ref "R56") (pin "1") (pinfunction "1_1") (pintype "passive"))
      (node (ref "RA1") (pin "2") (pinfunction "2_2") (pintype "passive"))
      (node (ref "RA10") (pin "2") (pinfunction "2_2") (pintype "passive"))
      (node (ref "RA11") (pin "2") (pinfunction "2_2") (pintype "passive"))
      (node (ref "RA12") (pin "2") (pinfunction "2_2") (pintype "passive"))
      (node (ref "RA2") (pin "2") (pinfunction "2_2") (pintype "passive"))
      (node (ref "RA3") (pin "2") (pinfunction "2_2") (pintype "passive"))
      (node (ref "RA4") (pin "2") (pinfunction "2_2") (pintype "passive"))
      (node (ref "RA5") (pin "2") (pinfunction "2_2") (pintype "passive"))
      (node (ref "RA6") (pin "2") (pinfunction "2_2") (pintype "passive"))
      (node (ref "RA7") (pin "2") (pinfunction "2_2") (pintype "passive"))
      (node (ref "RA8") (pin "2") (pinfunction "2_2") (pintype "passive"))
      (node (ref "RA9") (pin "2") (pinfunction "2_2") (pintype "passive"))
    )
    (net (code "5") (name "/1280_HANG_CHK") (class "Default")
      (node (ref "IC2") (pin "14") (pinfunction "PH2(XCK2)_14") (pintype "bidirectional"))
      (node (ref "JP7") (pin "10") (pinfunction "10_10") (pintype "passive"))
    )
    (net (code "6") (name "/ADC0") (class "Default")
      (node (ref "IC2") (pin "26") (pinfunction "(OC0A/OC1C/PCINT7)PB7_26") (pintype "bidirectional"))
      (node (ref "JP6") (pin "8") (pinfunction "8_8") (pintype "passive"))
      (node (ref "JP7") (pin "11") (pinfunction "11_11") (pintype "passive"))
      (node (ref "PWM") (pin "1") (pinfunction "1_1") (pintype "passive"))
    )
    (net (code "7") (name "/ADC1") (class "Default")
      (node (ref "IC2") (pin "25") (pinfunction "(OC1B/PCINT6)PB6_25") (pintype "bidirectional"))
      (node (ref "JP6") (pin "7") (pinfunction "7_7") (pintype "passive"))
      (node (ref "JP7") (pin "13") (pinfunction "13_13") (pintype "passive"))
      (node (ref "PWM") (pin "2") (pinfunction "2_2") (pintype "passive"))
    )
    (net (code "8") (name "/ADC2") (class "Default")
      (node (ref "IC2") (pin "24") (pinfunction "(OC1A/PCINT5)PB5_24") (pintype "bidirectional"))
      (node (ref "JP6") (pin "6") (pinfunction "6_6") (pintype "passive"))
      (node (ref "JP7") (pin "15") (pinfunction "15_15") (pintype "passive"))
      (node (ref "PWM") (pin "3") (pinfunction "3_3") (pintype "passive"))
    )
    (net (code "9") (name "/ADC3") (class "Default")
      (node (ref "IC2") (pin "23") (pinfunction "(OC2A/PCINT4)PB4_23") (pintype "bidirectional"))
      (node (ref "JP6") (pin "5") (pinfunction "5_5") (pintype "passive"))
      (node (ref "JP7") (pin "17") (pinfunction "17_17") (pintype "passive"))
      (node (ref "PWM") (pin "4") (pinfunction "4_4") (pintype "passive"))
    )
    (net (code "10") (name "/ADC4") (class "Default")
      (node (ref "JP6") (pin "4") (pinfunction "4_4") (pintype "passive"))
      (node (ref "JP7") (pin "19") (pinfunction "19_19") (pintype "passive"))
    )
    (net (code "11") (name "/ADC5") (class "Default")
      (node (ref "JP6") (pin "3") (pinfunction "3_3") (pintype "passive"))
      (node (ref "JP7") (pin "21") (pinfunction "21_21") (pintype "passive"))
    )
    (net (code "12") (name "/ADC6") (class "Default")
      (node (ref "JP6") (pin "2") (pinfunction "2_2") (pintype "passive"))
      (node (ref "JP7") (pin "23") (pinfunction "23_23") (pintype "passive"))
    )
    (net (code "13") (name "/ADC7") (class "Default")
      (node (ref "JP6") (pin "1") (pinfunction "1_1") (pintype "passive"))
      (node (ref "JP7") (pin "25") (pinfunction "25_25") (pintype "passive"))
    )
    (net (code "14") (name "/ADC8") (class "Default")
      (node (ref "JP5") (pin "1") (pinfunction "1_1") (pintype "passive"))
      (node (ref "JP7") (pin "12") (pinfunction "12_12") (pintype "passive"))
    )
    (net (code "15") (name "/ADC9") (class "Default")
      (node (ref "JP5") (pin "2") (pinfunction "2_2") (pintype "passive"))
      (node (ref "JP7") (pin "14") (pinfunction "14_14") (pintype "passive"))
    )
    (net (code "16") (name "/ADC10") (class "Default")
      (node (ref "JP5") (pin "3") (pinfunction "3_3") (pintype "passive"))
      (node (ref "JP7") (pin "16") (pinfunction "16_16") (pintype "passive"))
    )
    (net (code "17") (name "/ADC11") (class "Default")
      (node (ref "JP5") (pin "4") (pinfunction "4_4") (pintype "passive"))
      (node (ref "JP7") (pin "18") (pinfunction "18_18") (pintype "passive"))
    )
    (net (code "18") (name "/ADC12") (class "Default")
      (node (ref "JP5") (pin "5") (pinfunction "5_5") (pintype "passive"))
      (node (ref "JP7") (pin "20") (pinfunction "20_20") (pintype "passive"))
    )
    (net (code "19") (name "/ADC13") (class "Default")
      (node (ref "JP5") (pin "6") (pinfunction "6_6") (pintype "passive"))
      (node (ref "JP7") (pin "22") (pinfunction "22_22") (pintype "passive"))
    )
    (net (code "20") (name "/ADC14") (class "Default")
      (node (ref "JP5") (pin "7") (pinfunction "7_7") (pintype "passive"))
      (node (ref "JP7") (pin "24") (pinfunction "24_24") (pintype "passive"))
    )
    (net (code "21") (name "/ADC15") (class "Default")
      (node (ref "JP5") (pin "8") (pinfunction "8_8") (pintype "passive"))
      (node (ref "JP7") (pin "26") (pinfunction "26_26") (pintype "passive"))
    )
    (net (code "22") (name "/ANALOG6") (class "Default")
      (node (ref "AN_PINS") (pin "2") (pinfunction "2_2") (pintype "passive"))
      (node (ref "IC2") (pin "89") (pinfunction "PK0(ADC8/PCINT16)_89") (pintype "bidirectional"))
    )
    (net (code "23") (name "/ANALOG7") (class "Default")
      (node (ref "AN_PINS") (pin "3") (pinfunction "3_3") (pintype "passive"))
      (node (ref "IC2") (pin "88") (pinfunction "PK1(ADC9/PCINT17)_88") (pintype "bidirectional"))
    )
    (net (code "24") (name "/ANALOG8") (class "Default")
      (node (ref "AN_PINS") (pin "4") (pinfunction "4_4") (pintype "passive"))
      (node (ref "IC2") (pin "87") (pinfunction "PK2(ADC10/PCINT18)_87") (pintype "bidirectional"))
    )
    (net (code "25") (name "/ANALOG9") (class "Default")
      (node (ref "AN_PINS") (pin "5") (pinfunction "5_5") (pintype "passive"))
      (node (ref "IC2") (pin "86") (pinfunction "PK3(ADC11/PCINT19)_86") (pintype "bidirectional"))
    )
    (net (code "26") (name "/ANALOG10") (class "Default")
      (node (ref "AN_PINS") (pin "6") (pinfunction "6_6") (pintype "passive"))
      (node (ref "IC2") (pin "85") (pinfunction "PK4(ADC12/PCINT20)_85") (pintype "bidirectional"))
    )
    (net (code "27") (name "/ANALOG11") (class "Default")
      (node (ref "AN_PINS") (pin "7") (pinfunction "7_7") (pintype "passive"))
      (node (ref "IC2") (pin "84") (pinfunction "PK5(ADC13/PCINT21)_84") (pintype "bidirectional"))
    )
    (net (code "28") (name "/ANALOG12") (class "Default")
      (node (ref "AN_PINS") (pin "8") (pinfunction "8_8") (pintype "passive"))
      (node (ref "IC2") (pin "83") (pinfunction "PK6(ADC14/PCINT22)_83") (pintype "bidirectional"))
    )
    (net (code "29") (name "/ENCODER1") (class "Default")
      (node (ref "ENC1") (pin "2") (pinfunction "2_2") (pintype "passive"))
      (node (ref "OPTO1") (pin "1") (pinfunction "A_1") (pintype "bidirectional"))
      (node (ref "R35") (pin "2") (pinfunction "2_2") (pintype "passive"))
    )
    (net (code "30") (name "/ENCODER2") (class "Default")
      (node (ref "ENC2") (pin "2") (pinfunction "2_2") (pintype "passive"))
      (node (ref "OPTO2") (pin "1") (pinfunction "A_1") (pintype "bidirectional"))
      (node (ref "R19") (pin "2") (pinfunction "2_2") (pintype "passive"))
    )
    (net (code "31") (name "/IR1") (class "Default")
      (node (ref "IR1") (pin "2") (pinfunction "2_2") (pintype "passive"))
      (node (ref "U9") (pin "19") (pinfunction "19-RA0/AN0_19") (pintype "bidirectional"))
    )
    (net (code "32") (name "/IR2") (class "Default")
      (node (ref "IR2") (pin "2") (pinfunction "2_2") (pintype "passive"))
      (node (ref "U9") (pin "20") (pinfunction "20-RA1/AN1_20") (pintype "bidirectional"))
    )
    (net (code "33") (name "/IR3") (class "Default")
      (node (ref "IR3") (pin "2") (pinfunction "2_2") (pintype "passive"))
      (node (ref "U9") (pin "21") (pinfunction "21-RP0/AN2/PGED1_21") (pintype "bidirectional"))
    )
    (net (code "34") (name "/IR4") (class "Default")
      (node (ref "IR4") (pin "2") (pinfunction "2_2") (pintype "passive"))
      (node (ref "U9") (pin "22") (pinfunction "22-RP1/AN3/PGEC1_22") (pintype "bidirectional"))
    )
    (net (code "35") (name "/IR5") (class "Default")
      (node (ref "IR5") (pin "2") (pinfunction "2_2") (pintype "passive"))
      (node (ref "U9") (pin "23") (pinfunction "AN4/RB2-23_23") (pintype "bidirectional"))
    )
    (net (code "36") (name "/IR6") (class "Default")
      (node (ref "IR6") (pin "2") (pinfunction "2_2") (pintype "passive"))
      (node (ref "U9") (pin "24") (pinfunction "AN5/RB3-24_24") (pintype "bidirectional"))
    )
    (net (code "37") (name "/IR7") (class "Default")
      (node (ref "IR7") (pin "2") (pinfunction "2_2") (pintype "passive"))
      (node (ref "U9") (pin "25") (pinfunction "AN6/RC0-25_25") (pintype "bidirectional"))
    )
    (net (code "38") (name "/IR8") (class "Default")
      (node (ref "IR8") (pin "2") (pinfunction "2_2") (pintype "passive"))
      (node (ref "U9") (pin "26") (pinfunction "AN7/RC1-26_26") (pintype "bidirectional"))
    )
    (net (code "39") (name "/IR9") (class "Default")
      (node (ref "IR9") (pin "2") (pinfunction "2_2") (pintype "passive"))
      (node (ref "U9") (pin "27") (pinfunction "AN8/RC2-27_27") (pintype "bidirectional"))
    )
    (net (code "40") (name "/IR10") (class "Default")
      (node (ref "IR10") (pin "2") (pinfunction "2_2") (pintype "passive"))
      (node (ref "U9") (pin "15") (pinfunction "15-RP15/AN9_15") (pintype "bidirectional"))
    )
    (net (code "41") (name "/IR11") (class "Default")
      (node (ref "IR11") (pin "2") (pinfunction "2_2") (pintype "passive"))
      (node (ref "U9") (pin "14") (pinfunction "14-RP14/AN10_14") (pintype "bidirectional"))
    )
    (net (code "42") (name "/IR12") (class "Default")
      (node (ref "IR12") (pin "2") (pinfunction "2_2") (pintype "passive"))
      (node (ref "U9") (pin "11") (pinfunction "11-RP13/AN11_11") (pintype "bidirectional"))
    )
    (net (code "43") (name "/IRPWR1") (class "Default")
      (node (ref "RPW1") (pin "2") (pinfunction "2_2") (pintype "passive"))
      (node (ref "U9") (pin "32") (pinfunction "TDO/RA8-32_32") (pintype "bidirectional"))
    )
    (net (code "44") (name "/IRPWR2") (class "Default")
      (node (ref "RPW2") (pin "2") (pinfunction "2_2") (pintype "passive"))
      (node (ref "U9") (pin "33") (pinfunction "RB4-33_33") (pintype "bidirectional"))
    )
    (net (code "45") (name "/IRPWR3") (class "Default")
      (node (ref "RPW3") (pin "2") (pinfunction "2_2") (pintype "passive"))
      (node (ref "U9") (pin "34") (pinfunction "SOSC0/T1CK/RA4-34_34") (pintype "bidirectional"))
    )
    (net (code "46") (name "/IRPWR4") (class "Default")
      (node (ref "RPW4") (pin "2") (pinfunction "2_2") (pintype "passive"))
      (node (ref "U9") (pin "35") (pinfunction "TDI/RA9-35_35") (pintype "bidirectional"))
    )
    (net (code "47") (name "/IRPWR5") (class "Default")
      (node (ref "RPW5") (pin "2") (pinfunction "2_2") (pintype "passive"))
      (node (ref "U9") (pin "36") (pinfunction "RC3-36_36") (pintype "bidirectional"))
    )
    (net (code "48") (name "/IRPWR6") (class "Default")
      (node (ref "RPW6") (pin "2") (pinfunction "2_2") (pintype "passive"))
      (node (ref "U9") (pin "37") (pinfunction "RC4-37_37") (pintype "bidirectional"))
    )
    (net (code "49") (name "/IRPWR7") (class "Default")
      (node (ref "RPW7") (pin "2") (pinfunction "2_2") (pintype "passive"))
      (node (ref "U9") (pin "38") (pinfunction "RC5-38_38") (pintype "bidirectional"))
    )
    (net (code "50") (name "/IRPWR8") (class "Default")
      (node (ref "RPW8") (pin "2") (pinfunction "2_2") (pintype "passive"))
      (node (ref "U9") (pin "44") (pinfunction "SCL1/RB8-44_44") (pintype "bidirectional"))
    )
    (net (code "51") (name "/IRPWR9") (class "Default")
      (node (ref "RPW9") (pin "2") (pinfunction "2_2") (pintype "passive"))
      (node (ref "U9") (pin "1") (pinfunction "1-RP9/SDA1_1") (pintype "bidirectional"))
    )
    (net (code "52") (name "/IRPWR10") (class "Default")
      (node (ref "RPW10") (pin "2") (pinfunction "2_2") (pintype "passive"))
      (node (ref "U9") (pin "10") (pinfunction "10-RP12/AN12_10") (pintype "bidirectional"))
    )
    (net (code "53") (name "/IRPWR11") (class "Default")
      (node (ref "RPW11") (pin "2") (pinfunction "2_2") (pintype "passive"))
      (node (ref "U9") (pin "12") (pinfunction "12-RA10/TMS_12") (pintype "bidirectional"))
    )
    (net (code "54") (name "/IRPWR12") (class "Default")
      (node (ref "RPW12") (pin "2") (pinfunction "2_2") (pintype "passive"))
      (node (ref "U9") (pin "13") (pinfunction "13-RA7/TCK_13") (pintype "bidirectional"))
    )
    (net (code "55") (name "/PB1") (class "Default")
      (node (ref "IC2") (pin "20") (pinfunction "(SCK/PCINT1)PB1_20") (pintype "bidirectional"))
      (node (ref "ICSP") (pin "3") (pinfunction "3_3") (pintype "passive"))
    )
    (net (code "56") (name "/PB2") (class "Default")
      (node (ref "IC2") (pin "21") (pinfunction "(MOSI/PCINT2)PB2_21") (pintype "bidirectional"))
      (node (ref "ICSP") (pin "4") (pinfunction "4_4") (pintype "passive"))
    )
    (net (code "57") (name "/PB3") (class "Default")
      (node (ref "IC2") (pin "22") (pinfunction "(MISO/PCINT3)PB3_22") (pintype "bidirectional"))
      (node (ref "ICSP") (pin "1") (pinfunction "1_1") (pintype "passive"))
    )
    (net (code "58") (name "/PICUSBRX") (class "Default")
      (node (ref "U9") (pin "43") (pinfunction "INT0/RB7-43_43") (pintype "bidirectional"))
      (node (ref "USBSEL") (pin "3") (pinfunction "3_3") (pintype "passive"))
    )
    (net (code "59") (name "/PICUSBTX") (class "Default")
      (node (ref "U9") (pin "42") (pinfunction "PGEC3/ASCL1/RB6-42_42") (pintype "bidirectional"))
      (node (ref "USBSEL") (pin "1") (pinfunction "1_1") (pintype "passive"))
    )
    (net (code "60") (name "/PIC_HANG_CHK") (class "Default")
      (node (ref "JP7") (pin "9") (pinfunction "9_9") (pintype "passive"))
      (node (ref "LED_TOG") (pin "1") (pinfunction "1_1") (pintype "passive"))
      (node (ref "R26") (pin "2") (pinfunction "2_2") (pintype "passive"))
    )
    (net (code "61") (name "/PROCESSORSELECTRX") (class "Default")
      (node (ref "IC4") (pin "5") (pinfunction "RXD_5") (pintype "input"))
      (node (ref "USBSEL") (pin "4") (pinfunction "4_4") (pintype "passive"))
      (node (ref "USBSEL") (pin "8") (pinfunction "8_8") (pintype "passive"))
    )
    (net (code "62") (name "/PROCESSORSELECTTX") (class "Default")
      (node (ref "R29") (pin "1") (pinfunction "1_1") (pintype "passive"))
      (node (ref "USBSEL") (pin "2") (pinfunction "2_2") (pintype "passive"))
      (node (ref "USBSEL") (pin "6") (pinfunction "6_6") (pintype "passive"))
    )
    (net (code "63") (name "/RESET") (class "Default")
      (node (ref "C3") (pin "1") (pinfunction "1_1") (pintype "passive"))
      (node (ref "IC2") (pin "30") (pinfunction "RESET_30") (pintype "input"))
      (node (ref "ICSP") (pin "5") (pinfunction "5_5") (pintype "passive"))
      (node (ref "R5") (pin "1") (pinfunction "1_1") (pintype "passive"))
      (node (ref "S1") (pin "3") (pinfunction "P_3") (pintype "passive"))
      (node (ref "S1") (pin "4") (pinfunction "P1_4") (pintype "passive"))
    )
    (net (code "64") (name "/RSA") (class "Default")
      (node (ref "JP7") (pin "2") (pinfunction "2_2") (pintype "passive"))
      (node (ref "RS485_HEADER") (pin "1") (pinfunction "1_1") (pintype "passive"))
      (node (ref "U1") (pin "8") (pinfunction "A_8") (pintype "bidirectional"))
    )
    (net (code "65") (name "/RSB") (class "Default")
      (node (ref "JP7") (pin "4") (pinfunction "4_4") (pintype "passive"))
      (node (ref "RS485_HEADER") (pin "2") (pinfunction "2_2") (pintype "passive"))
      (node (ref "U1") (pin "7") (pinfunction "B_7") (pintype "bidirectional"))
    )
    (net (code "66") (name "/RSY") (class "Default")
      (node (ref "JP7") (pin "8") (pinfunction "8_8") (pintype "passive"))
      (node (ref "RS485_HEADER") (pin "4") (pinfunction "4_4") (pintype "passive"))
      (node (ref "U1") (pin "5") (pinfunction "Y_5") (pintype "bidirectional"))
    )
    (net (code "67") (name "/RSZ") (class "Default")
      (node (ref "JP7") (pin "6") (pinfunction "6_6") (pintype "passive"))
      (node (ref "RS485_HEADER") (pin "3") (pinfunction "3_3") (pintype "passive"))
      (node (ref "U1") (pin "6") (pinfunction "Z_6") (pintype "bidirectional"))
    )
    (net (code "68") (name "/RXD0") (class "Default")
      (node (ref "IC2") (pin "2") (pinfunction "(RXD0/PCIN8)PE0_2") (pintype "bidirectional"))
      (node (ref "LED5") (pin "C") (pinfunction "C_C") (pintype "passive"))
      (node (ref "UART0") (pin "2") (pinfunction "2_2") (pintype "passive"))
      (node (ref "USBSEL") (pin "7") (pinfunction "7_7") (pintype "passive"))
    )
    (net (code "69") (name "/RXD1") (class "Default")
      (node (ref "COTL_BOX") (pin "3") (pinfunction "3_3") (pintype "passive"))
      (node (ref "IC2") (pin "46") (pinfunction "(TXD1/INT3)PD3_46") (pintype "bidirectional"))
      (node (ref "JP7") (pin "3") (pinfunction "3_3") (pintype "passive"))
    )
    (net (code "70") (name "/RXD2") (class "Default")
      (node (ref "IC2") (pin "12") (pinfunction "PH0(RXD2)_12") (pintype "bidirectional"))
      (node (ref "LED8") (pin "C") (pinfunction "C_C") (pintype "passive"))
      (node (ref "U1") (pin "3") (pinfunction "DI_3") (pintype "bidirectional"))
      (node (ref "UART2") (pin "2") (pinfunction "2_2") (pintype "passive"))
    )
    (net (code "71") (name "/RXD3") (class "Default")
      (node (ref "IC2") (pin "63") (pinfunction "PJ0(RXD3/PCINT9)_63") (pintype "bidirectional"))
      (node (ref "JP7") (pin "7") (pinfunction "7_7") (pintype "passive"))
      (node (ref "LED1") (pin "C") (pinfunction "C_C") (pintype "passive"))
      (node (ref "U9") (pin "2") (pinfunction "2-RP22_2") (pintype "bidirectional"))
      (node (ref "UART3") (pin "2") (pinfunction "2_2") (pintype "passive"))
    )
    (net (code "72") (name "/TXD0") (class "Default")
      (node (ref "IC2") (pin "3") (pinfunction "(TXD0)PE1_3") (pintype "bidirectional"))
      (node (ref "LED6") (pin "C") (pinfunction "C_C") (pintype "passive"))
      (node (ref "UART0") (pin "1") (pinfunction "1_1") (pintype "passive"))
      (node (ref "USBSEL") (pin "5") (pinfunction "5_5") (pintype "passive"))
    )
    (net (code "73") (name "/TXD1") (class "Default")
      (node (ref "COTL_BOX") (pin "2") (pinfunction "2_2") (pintype "passive"))
      (node (ref "IC2") (pin "45") (pinfunction "(RXD1/INT2)PD2_45") (pintype "bidirectional"))
      (node (ref "JP7") (pin "5") (pinfunction "5_5") (pintype "passive"))
    )
    (net (code "74") (name "/TXD2") (class "Default")
      (node (ref "IC2") (pin "13") (pinfunction "PH1(TXD2)_13") (pintype "bidirectional"))
      (node (ref "LED10") (pin "C") (pinfunction "C_C") (pintype "passive"))
      (node (ref "U1") (pin "2") (pinfunction "RO_2") (pintype "bidirectional"))
      (node (ref "UART2") (pin "3") (pinfunction "3_3") (pintype "passive"))
    )
    (net (code "75") (name "/TXD3") (class "Default")
      (node (ref "IC2") (pin "64") (pinfunction "PJ1(TXD3/PCINT10)_64") (pintype "bidirectional"))
      (node (ref "LED2") (pin "C") (pinfunction "C_C") (pintype "passive"))
      (node (ref "U9") (pin "3") (pinfunction "3-RP23_3") (pintype "bidirectional"))
      (node (ref "UART3") (pin "3") (pinfunction "3_3") (pintype "passive"))
    )
    (net (code "76") (name "/~{MCLR}") (class "Default")
      (node (ref "R25") (pin "1") (pinfunction "1_1") (pintype "passive"))
      (node (ref "S2") (pin "4") (pinfunction "P1_4") (pintype "passive"))
      (node (ref "U9") (pin "18") (pinfunction "18-~{MCLR}_18") (pintype "bidirectional"))
    )
    (net (code "77") (name "GND") (class "Default")
      (node (ref "AN_PINS") (pin "1") (pinfunction "1_1") (pintype "passive"))
      (node (ref "C1") (pin "C") (pinfunction "-_C") (pintype "passive"))
      (node (ref "C16") (pin "2") (pinfunction "2_2") (pintype "passive"))
      (node (ref "C17") (pin "2") (pinfunction "2_2") (pintype "passive"))
      (node (ref "C18") (pin "C") (pinfunction "-_C") (pintype "passive"))
      (node (ref "C2") (pin "2") (pinfunction "2_2") (pintype "passive"))
      (node (ref "C27") (pin "2") (pinfunction "2_2") (pintype "passive"))
      (node (ref "C29") (pin "2") (pinfunction "2_2") (pintype "passive"))
      (node (ref "C3") (pin "2") (pinfunction "2_2") (pintype "passive"))
      (node (ref "C4") (pin "2") (pinfunction "2_2") (pintype "passive"))
      (node (ref "C5") (pin "C") (pinfunction "-_C") (pintype "passive"))
      (node (ref "C69") (pin "2") (pinfunction "2_2") (pintype "passive"))
      (node (ref "C82") (pin "2") (pinfunction "-_2") (pintype "passive"))
      (node (ref "CAN1") (pin "-") (pinfunction "-_-") (pintype "passive"))
      (node (ref "CAN2") (pin "-") (pinfunction "-_-") (pintype "passive"))
      (node (ref "CAN3") (pin "-") (pinfunction "-_-") (pintype "passive"))
      (node (ref "CN3") (pin "GND") (pinfunction "GND_GND") (pintype "power_in"))
      (node (ref "COTL_BOX") (pin "1") (pinfunction "1_1") (pintype "passive"))
      (node (ref "DC-DC") (pin "3") (pinfunction "GND_3") (pintype "bidirectional"))
      (node (ref "DC-DC") (pin "G") (pinfunction "GND_G") (pintype "bidirectional"))
      (node (ref "ENC1") (pin "3") (pinfunction "3_3") (pintype "passive"))
      (node (ref "ENC2") (pin "3") (pinfunction "3_3") (pintype "passive"))
      (node (ref "GYRO") (pin "4") (pinfunction "4_4") (pintype "passive"))
      (node (ref "H1") (pin "B5,5") (pinfunction "MOUNT_B5,5") (pintype "passive"))
      (node (ref "H2") (pin "B5,5") (pinfunction "MOUNT_B5,5") (pintype "passive"))
      (node (ref "H3") (pin "B5,5") (pinfunction "MOUNT_B5,5") (pintype "passive"))
      (node (ref "H4") (pin "B5,5") (pinfunction "MOUNT_B5,5") (pintype "passive"))
      (node (ref "IC2") (pin "11") (pinfunction "GND_11") (pintype "power_in"))
      (node (ref "IC2") (pin "32") (pinfunction "GND1_32") (pintype "power_in"))
      (node (ref "IC2") (pin "62") (pinfunction "GND2_62") (pintype "power_in"))
      (node (ref "IC2") (pin "81") (pinfunction "GND3_81") (pintype "power_in"))
      (node (ref "IC2") (pin "99") (pinfunction "AGND_99") (pintype "power_in"))
      (node (ref "IC4") (pin "18") (pinfunction "GND_18") (pintype "input"))
      (node (ref "IC4") (pin "21") (pinfunction "GND_21") (pintype "input"))
      (node (ref "IC4") (pin "25") (pinfunction "GND_25") (pintype "input"))
      (node (ref "IC4") (pin "26") (pinfunction "TEST_26") (pintype "input"))
      (node (ref "IC4") (pin "7") (pinfunction "GND_7") (pintype "input"))
      (node (ref "ICSP") (pin "6") (pinfunction "6_6") (pintype "passive"))
      (node (ref "IR1") (pin "3") (pinfunction "3_3") (pintype "passive"))
      (node (ref "IR10") (pin "3") (pinfunction "3_3") (pintype "passive"))
      (node (ref "IR11") (pin "3") (pinfunction "3_3") (pintype "passive"))
      (node (ref "IR12") (pin "3") (pinfunction "3_3") (pintype "passive"))
      (node (ref "IR2") (pin "3") (pinfunction "3_3") (pintype "passive"))
      (node (ref "IR3") (pin "3") (pinfunction "3_3") (pintype "passive"))
      (node (ref "IR4") (pin "3") (pinfunction "3_3") (pintype "passive"))
      (node (ref "IR5") (pin "3") (pinfunction "3_3") (pintype "passive"))
      (node (ref "IR6") (pin "3") (pinfunction "3_3") (pintype "passive"))
      (node (ref "IR7") (pin "3") (pinfunction "3_3") (pintype "passive"))
      (node (ref "IR8") (pin "3") (pinfunction "3_3") (pintype "passive"))
      (node (ref "IR9") (pin "3") (pinfunction "3_3") (pintype "passive"))
      (node (ref "OPTO1") (pin "2") (pinfunction "K_2") (pintype "bidirectional"))
      (node (ref "OPTO2") (pin "2") (pinfunction "K_2") (pintype "bidirectional"))
      (node (ref "OPTO2") (pin "3") (pinfunction "E_3") (pintype "bidirectional"))
      (node (ref "PIC_PROG") (pin "3") (pinfunction "3_3") (pintype "passive"))
      (node (ref "POWER") (pin "1") (pinfunction "1_1") (pintype "passive"))
      (node (ref "PWR_5V") (pin "C") (pinfunction "C_C") (pintype "passive"))
      (node (ref "PWR_9V") (pin "C") (pinfunction "C_C") (pintype "passive"))
      (node (ref "PWR_IR") (pin "C") (pinfunction "C_C") (pintype "passive"))
      (node (ref "QB1") (pin "2") (pinfunction "E_2") (pintype "passive"))
      (node (ref "QB10") (pin "2") (pinfunction "E_2") (pintype "passive"))
      (node (ref "QB11") (pin "2") (pinfunction "E_2") (pintype "passive"))
      (node (ref "QB12") (pin "2") (pinfunction "E_2") (pintype "passive"))
      (node (ref "QB2") (pin "2") (pinfunction "E_2") (pintype "passive"))
      (node (ref "QB3") (pin "2") (pinfunction "E_2") (pintype "passive"))
      (node (ref "QB4") (pin "2") (pinfunction "E_2") (pintype "passive"))
      (node (ref "QB5") (pin "2") (pinfunction "E_2") (pintype "passive"))
      (node (ref "QB6") (pin "2") (pinfunction "E_2") (pintype "passive"))
      (node (ref "QB7") (pin "2") (pinfunction "E_2") (pintype "passive"))
      (node (ref "QB8") (pin "2") (pinfunction "E_2") (pintype "passive"))
      (node (ref "QB9") (pin "2") (pinfunction "E_2") (pintype "passive"))
      (node (ref "S1") (pin "1") (pinfunction "S_1") (pintype "passive"))
      (node (ref "S1") (pin "2") (pinfunction "S1_2") (pintype "passive"))
      (node (ref "S2") (pin "2") (pinfunction "S1_2") (pintype "passive"))
      (node (ref "U$1") (pin "2") (pinfunction "GND_2") (pintype "bidirectional"))
      (node (ref "U1") (pin "4") (pinfunction "GND_4") (pintype "bidirectional"))
      (node (ref "U9") (pin "16") (pinfunction "16-AVSS_16") (pintype "bidirectional"))
      (node (ref "U9") (pin "29") (pinfunction "VSS-29_29") (pintype "bidirectional"))
      (node (ref "U9") (pin "39") (pinfunction "VSS-39_39") (pintype "bidirectional"))
      (node (ref "U9") (pin "6") (pinfunction "6-VSS_6") (pintype "bidirectional"))
      (node (ref "UART0") (pin "3") (pinfunction "3_3") (pintype "passive"))
      (node (ref "UART2") (pin "1") (pinfunction "1_1") (pintype "passive"))
      (node (ref "UART3") (pin "1") (pinfunction "1_1") (pintype "passive"))
    )
    (net (code "78") (name "GNDIO") (class "Default")
      (node (ref "PIC_LED") (pin "C") (pinfunction "C_C") (pintype "passive"))
    )
    (net (code "79") (name "Net-(C69-Pad1)") (class "Default")
      (node (ref "C69") (pin "1") (pinfunction "1_1") (pintype "passive"))
      (node (ref "PIC_PROG") (pin "1") (pinfunction "1_1") (pintype "passive"))
      (node (ref "R120") (pin "1") (pinfunction "1_1") (pintype "passive"))
      (node (ref "R25") (pin "2") (pinfunction "2_2") (pintype "passive"))
    )
    (net (code "80") (name "Net-(C82-+)") (class "Default")
      (node (ref "C82") (pin "1") (pinfunction "+_1") (pintype "passive"))
      (node (ref "U9") (pin "7") (pinfunction "7-VCAP_7") (pintype "bidirectional"))
    )
    (net (code "81") (name "Net-(IC2-(OC3A{slash}AIN1)PE3)") (class "Default")
      (node (ref "IC2") (pin "5") (pinfunction "(OC3A/AIN1)PE3_5") (pintype "bidirectional"))
      (node (ref "PWM2") (pin "3") (pinfunction "3_3") (pintype "passive"))
    )
    (net (code "82") (name "Net-(IC2-(OC3B{slash}INT4)PE4)") (class "Default")
      (node (ref "IC2") (pin "6") (pinfunction "(OC3B/INT4)PE4_6") (pintype "bidirectional"))
      (node (ref "PWM2") (pin "2") (pinfunction "2_2") (pintype "passive"))
    )
    (net (code "83") (name "Net-(IC2-(OC3C{slash}INT5)PE5)") (class "Default")
      (node (ref "IC2") (pin "7") (pinfunction "(OC3C/INT5)PE5_7") (pintype "bidirectional"))
      (node (ref "PWM2") (pin "1") (pinfunction "1_1") (pintype "passive"))
    )
    (net (code "84") (name "Net-(IC2-(SCL{slash}INT0)PD0)") (class "Default")
      (node (ref "GYRO") (pin "3") (pinfunction "3_3") (pintype "passive"))
      (node (ref "IC2") (pin "43") (pinfunction "(SCL/INT0)PD0_43") (pintype "bidirectional"))
      (node (ref "R37") (pin "2") (pinfunction "2_2") (pintype "passive"))
    )
    (net (code "85") (name "Net-(IC2-(SDA{slash}INT1)PD1)") (class "Default")
      (node (ref "GYRO") (pin "2") (pinfunction "2_2") (pintype "passive"))
      (node (ref "IC2") (pin "44") (pinfunction "(SDA/INT1)PD1_44") (pintype "bidirectional"))
      (node (ref "R38") (pin "2") (pinfunction "2_2") (pintype "passive"))
    )
    (net (code "86") (name "Net-(IC2-PL0(ICP4))") (class "Default")
      (node (ref "DIG1") (pin "1") (pinfunction "1_1") (pintype "passive"))
      (node (ref "IC2") (pin "35") (pinfunction "PL0(ICP4)_35") (pintype "bidirectional"))
    )
    (net (code "87") (name "Net-(IC2-PL1(ICP5))") (class "Default")
      (node (ref "DIG1") (pin "2") (pinfunction "2_2") (pintype "passive"))
      (node (ref "IC2") (pin "36") (pinfunction "PL1(ICP5)_36") (pintype "bidirectional"))
    )
    (net (code "88") (name "Net-(IC2-PL2(T5))") (class "Default")
      (node (ref "DIG1") (pin "3") (pinfunction "3_3") (pintype "passive"))
      (node (ref "IC2") (pin "37") (pinfunction "PL2(T5)_37") (pintype "bidirectional"))
    )
    (net (code "89") (name "Net-(IC2-PL3(OC5A))") (class "Default")
      (node (ref "DIG2") (pin "1") (pinfunction "1_1") (pintype "passive"))
      (node (ref "IC2") (pin "38") (pinfunction "PL3(OC5A)_38") (pintype "bidirectional"))
    )
    (net (code "90") (name "Net-(IC2-PL4(OC5B))") (class "Default")
      (node (ref "DIG2") (pin "2") (pinfunction "2_2") (pintype "passive"))
      (node (ref "IC2") (pin "39") (pinfunction "PL4(OC5B)_39") (pintype "bidirectional"))
    )
    (net (code "91") (name "Net-(IC2-PL5(OC5C))") (class "Default")
      (node (ref "DIG2") (pin "3") (pinfunction "3_3") (pintype "passive"))
      (node (ref "IC2") (pin "40") (pinfunction "PL5(OC5C)_40") (pintype "bidirectional"))
    )
    (net (code "92") (name "Net-(IC2-XTAL1)") (class "Default")
      (node (ref "IC2") (pin "34") (pinfunction "XTAL1_34") (pintype "input"))
      (node (ref "U$1") (pin "3") (pinfunction "OUT_3") (pintype "bidirectional"))
    )
    (net (code "93") (name "Net-(IC2-XTAL2)") (class "Default")
      (node (ref "IC2") (pin "33") (pinfunction "XTAL2_33") (pintype "output"))
      (node (ref "U$1") (pin "1") (pinfunction "IN_1") (pintype "bidirectional"))
    )
    (net (code "94") (name "Net-(IC4-3V3OUT)") (class "Default")
      (node (ref "C17") (pin "1") (pinfunction "1_1") (pintype "passive"))
      (node (ref "IC4") (pin "17") (pinfunction "3V3OUT_17") (pintype "input"))
      (node (ref "IC4") (pin "4") (pinfunction "VCCIO_4") (pintype "input"))
    )
    (net (code "95") (name "Net-(IC4-CBUS0)") (class "Default")
      (node (ref "IC4") (pin "23") (pinfunction "CBUS0_23") (pintype "input"))
      (node (ref "TX3") (pin "C") (pinfunction "C_C") (pintype "passive"))
    )
    (net (code "96") (name "Net-(IC4-CBUS1)") (class "Default")
      (node (ref "IC4") (pin "22") (pinfunction "CBUS1_22") (pintype "input"))
      (node (ref "RX3") (pin "C") (pinfunction "C_C") (pintype "passive"))
    )
    (net (code "97") (name "Net-(IC4-TXD)") (class "Default")
      (node (ref "IC4") (pin "1") (pinfunction "TXD_1") (pintype "input"))
      (node (ref "R29") (pin "2") (pinfunction "2_2") (pintype "passive"))
    )
    (net (code "98") (name "Net-(IC4-USBDM)") (class "Default")
      (node (ref "CN3") (pin "D-") (pinfunction "D-_D-") (pintype "bidirectional"))
      (node (ref "IC4") (pin "16") (pinfunction "USBDM_16") (pintype "input"))
    )
    (net (code "99") (name "Net-(IC4-USBDP)") (class "Default")
      (node (ref "CN3") (pin "D+") (pinfunction "D+_D+") (pintype "bidirectional"))
      (node (ref "IC4") (pin "15") (pinfunction "USBDP_15") (pintype "input"))
    )
    (net (code "100") (name "Net-(L3-P$2)") (class "Default")
      (node (ref "C27") (pin "1") (pinfunction "1_1") (pintype "passive"))
      (node (ref "L3") (pin "2") (pinfunction "P$2_2") (pintype "bidirectional"))
      (node (ref "U9") (pin "17") (pinfunction "17-AVDD_17") (pintype "bidirectional"))
    )
    (net (code "101") (name "Net-(LED1-PadA)") (class "Default")
      (node (ref "LED1") (pin "A") (pinfunction "A_A") (pintype "passive"))
      (node (ref "R1") (pin "1") (pinfunction "1_1") (pintype "passive"))
    )
    (net (code "102") (name "Net-(LED2-PadA)") (class "Default")
      (node (ref "LED2") (pin "A") (pinfunction "A_A") (pintype "passive"))
      (node (ref "R9") (pin "1") (pinfunction "1_1") (pintype "passive"))
    )
    (net (code "103") (name "Net-(LED5-PadA)") (class "Default")
      (node (ref "LED5") (pin "A") (pinfunction "A_A") (pintype "passive"))
      (node (ref "R10") (pin "1") (pinfunction "1_1") (pintype "passive"))
    )
    (net (code "104") (name "Net-(LED6-PadA)") (class "Default")
      (node (ref "LED6") (pin "A") (pinfunction "A_A") (pintype "passive"))
      (node (ref "R11") (pin "1") (pinfunction "1_1") (pintype "passive"))
    )
    (net (code "105") (name "Net-(LED8-PadA)") (class "Default")
      (node (ref "LED8") (pin "A") (pinfunction "A_A") (pintype "passive"))
      (node (ref "R12") (pin "1") (pinfunction "1_1") (pintype "passive"))
    )
    (net (code "106") (name "Net-(LED10-PadA)") (class "Default")
      (node (ref "LED10") (pin "A") (pinfunction "A_A") (pintype "passive"))
      (node (ref "R13") (pin "1") (pinfunction "1_1") (pintype "passive"))
    )
    (net (code "107") (name "Net-(OPTO1-C)") (class "Default")
      (node (ref "OPTO1") (pin "4") (pinfunction "C_4") (pintype "bidirectional"))
      (node (ref "R17") (pin "1") (pinfunction "1_1") (pintype "passive"))
      (node (ref "U9") (pin "4") (pinfunction "4-RP24_4") (pintype "bidirectional"))
    )
    (net (code "108") (name "Net-(OPTO2-C)") (class "Default")
      (node (ref "OPTO2") (pin "4") (pinfunction "C_4") (pintype "bidirectional"))
      (node (ref "R4") (pin "1") (pinfunction "1_1") (pintype "passive"))
      (node (ref "U9") (pin "5") (pinfunction "5-RP25_5") (pintype "bidirectional"))
    )
    (net (code "109") (name "Net-(PIC_LED-PadA)") (class "Default")
      (node (ref "PIC_LED") (pin "A") (pinfunction "A_A") (pintype "passive"))
      (node (ref "R26") (pin "1") (pinfunction "1_1") (pintype "passive"))
    )
    (net (code "110") (name "Net-(PWR_5V-PadA)") (class "Default")
      (node (ref "PWR_5V") (pin "A") (pinfunction "A_A") (pintype "passive"))
      (node (ref "R8") (pin "2") (pinfunction "2_2") (pintype "passive"))
    )
    (net (code "111") (name "Net-(PWR_9V-PadA)") (class "Default")
      (node (ref "PWR_9V") (pin "A") (pinfunction "A_A") (pintype "passive"))
      (node (ref "R57") (pin "2") (pinfunction "2_2") (pintype "passive"))
    )
    (net (code "112") (name "Net-(PWR_IR-PadA)") (class "Default")
      (node (ref "PWR_IR") (pin "A") (pinfunction "A_A") (pintype "passive"))
      (node (ref "R56") (pin "2") (pinfunction "2_2") (pintype "passive"))
    )
    (net (code "113") (name "Net-(QA1-B)") (class "Default")
      (node (ref "QA1") (pin "1") (pinfunction "B_1") (pintype "passive"))
      (node (ref "RB1") (pin "2") (pinfunction "2_2") (pintype "passive"))
    )
    (net (code "114") (name "Net-(QA1-C)") (class "Default")
      (node (ref "IR1") (pin "1") (pinfunction "1_1") (pintype "passive"))
      (node (ref "QA1") (pin "3") (pinfunction "C_3") (pintype "passive"))
    )
    (net (code "115") (name "Net-(QA2-B)") (class "Default")
      (node (ref "QA2") (pin "1") (pinfunction "B_1") (pintype "passive"))
      (node (ref "RB2") (pin "2") (pinfunction "2_2") (pintype "passive"))
    )
    (net (code "116") (name "Net-(QA2-C)") (class "Default")
      (node (ref "IR2") (pin "1") (pinfunction "1_1") (pintype "passive"))
      (node (ref "QA2") (pin "3") (pinfunction "C_3") (pintype "passive"))
    )
    (net (code "117") (name "Net-(QA3-B)") (class "Default")
      (node (ref "QA3") (pin "1") (pinfunction "B_1") (pintype "passive"))
      (node (ref "RB3") (pin "2") (pinfunction "2_2") (pintype "passive"))
    )
    (net (code "118") (name "Net-(QA3-C)") (class "Default")
      (node (ref "IR3") (pin "1") (pinfunction "1_1") (pintype "passive"))
      (node (ref "QA3") (pin "3") (pinfunction "C_3") (pintype "passive"))
    )
    (net (code "119") (name "Net-(QA4-B)") (class "Default")
      (node (ref "QA4") (pin "1") (pinfunction "B_1") (pintype "passive"))
      (node (ref "RB4") (pin "2") (pinfunction "2_2") (pintype "passive"))
    )
    (net (code "120") (name "Net-(QA4-C)") (class "Default")
      (node (ref "IR4") (pin "1") (pinfunction "1_1") (pintype "passive"))
      (node (ref "QA4") (pin "3") (pinfunction "C_3") (pintype "passive"))
    )
    (net (code "121") (name "Net-(QA5-B)") (class "Default")
      (node (ref "QA5") (pin "1") (pinfunction "B_1") (pintype "passive"))
      (node (ref "RB5") (pin "2") (pinfunction "2_2") (pintype "passive"))
    )
    (net (code "122") (name "Net-(QA5-C)") (class "Default")
      (node (ref "IR5") (pin "1") (pinfunction "1_1") (pintype "passive"))
      (node (ref "QA5") (pin "3") (pinfunction "C_3") (pintype "passive"))
    )
    (net (code "123") (name "Net-(QA6-B)") (class "Default")
      (node (ref "QA6") (pin "1") (pinfunction "B_1") (pintype "passive"))
      (node (ref "RB6") (pin "2") (pinfunction "2_2") (pintype "passive"))
    )
    (net (code "124") (name "Net-(QA6-C)") (class "Default")
      (node (ref "IR6") (pin "1") (pinfunction "1_1") (pintype "passive"))
      (node (ref "QA6") (pin "3") (pinfunction "C_3") (pintype "passive"))
    )
    (net (code "125") (name "Net-(QA7-B)") (class "Default")
      (node (ref "QA7") (pin "1") (pinfunction "B_1") (pintype "passive"))
      (node (ref "RB7") (pin "2") (pinfunction "2_2") (pintype "passive"))
    )
    (net (code "126") (name "Net-(QA7-C)") (class "Default")
      (node (ref "IR7") (pin "1") (pinfunction "1_1") (pintype "passive"))
      (node (ref "QA7") (pin "3") (pinfunction "C_3") (pintype "passive"))
    )
    (net (code "127") (name "Net-(QA8-B)") (class "Default")
      (node (ref "QA8") (pin "1") (pinfunction "B_1") (pintype "passive"))
      (node (ref "RB8") (pin "2") (pinfunction "2_2") (pintype "passive"))
    )
    (net (code "128") (name "Net-(QA8-C)") (class "Default")
      (node (ref "IR8") (pin "1") (pinfunction "1_1") (pintype "passive"))
      (node (ref "QA8") (pin "3") (pinfunction "C_3") (pintype "passive"))
    )
    (net (code "129") (name "Net-(QA9-B)") (class "Default")
      (node (ref "QA9") (pin "1") (pinfunction "B_1") (pintype "passive"))
      (node (ref "RB9") (pin "2") (pinfunction "2_2") (pintype "passive"))
    )
    (net (code "130") (name "Net-(QA9-C)") (class "Default")
      (node (ref "IR9") (pin "1") (pinfunction "1_1") (pintype "passive"))
      (node (ref "QA9") (pin "3") (pinfunction "C_3") (pintype "passive"))
    )
    (net (code "131") (name "Net-(QA10-B)") (class "Default")
      (node (ref "QA10") (pin "1") (pinfunction "B_1") (pintype "passive"))
      (node (ref "RB10") (pin "2") (pinfunction "2_2") (pintype "passive"))
    )
    (net (code "132") (name "Net-(QA10-C)") (class "Default")
      (node (ref "IR10") (pin "1") (pinfunction "1_1") (pintype "passive"))
      (node (ref "QA10") (pin "3") (pinfunction "C_3") (pintype "passive"))
    )
    (net (code "133") (name "Net-(QA11-B)") (class "Default")
      (node (ref "QA11") (pin "1") (pinfunction "B_1") (pintype "passive"))
      (node (ref "RB11") (pin "2") (pinfunction "2_2") (pintype "passive"))
    )
    (net (code "134") (name "Net-(QA11-C)") (class "Default")
      (node (ref "IR11") (pin "1") (pinfunction "1_1") (pintype "passive"))
      (node (ref "QA11") (pin "3") (pinfunction "C_3") (pintype "passive"))
    )
    (net (code "135") (name "Net-(QA12-B)") (class "Default")
      (node (ref "QA12") (pin "1") (pinfunction "B_1") (pintype "passive"))
      (node (ref "RB12") (pin "2") (pinfunction "2_2") (pintype "passive"))
    )
    (net (code "136") (name "Net-(QA12-C)") (class "Default")
      (node (ref "IR12") (pin "1") (pinfunction "1_1") (pintype "passive"))
      (node (ref "QA12") (pin "3") (pinfunction "C_3") (pintype "passive"))
    )
    (net (code "137") (name "Net-(QB1-B)") (class "Default")
      (node (ref "QB1") (pin "1") (pinfunction "B_1") (pintype "passive"))
      (node (ref "RPW1") (pin "1") (pinfunction "1_1") (pintype "passive"))
    )
    (net (code "138") (name "Net-(QB1-C)") (class "Default")
      (node (ref "QB1") (pin "3") (pinfunction "C_3") (pintype "passive"))
      (node (ref "RA1") (pin "1") (pinfunction "1_1") (pintype "passive"))
      (node (ref "RB1") (pin "1") (pinfunction "1_1") (pintype "passive"))
    )
    (net (code "139") (name "Net-(QB2-B)") (class "Default")
      (node (ref "QB2") (pin "1") (pinfunction "B_1") (pintype "passive"))
      (node (ref "RPW2") (pin "1") (pinfunction "1_1") (pintype "passive"))
    )
    (net (code "140") (name "Net-(QB2-C)") (class "Default")
      (node (ref "QB2") (pin "3") (pinfunction "C_3") (pintype "passive"))
      (node (ref "RA2") (pin "1") (pinfunction "1_1") (pintype "passive"))
      (node (ref "RB2") (pin "1") (pinfunction "1_1") (pintype "passive"))
    )
    (net (code "141") (name "Net-(QB3-B)") (class "Default")
      (node (ref "QB3") (pin "1") (pinfunction "B_1") (pintype "passive"))
      (node (ref "RPW3") (pin "1") (pinfunction "1_1") (pintype "passive"))
    )
    (net (code "142") (name "Net-(QB3-C)") (class "Default")
      (node (ref "QB3") (pin "3") (pinfunction "C_3") (pintype "passive"))
      (node (ref "RA3") (pin "1") (pinfunction "1_1") (pintype "passive"))
      (node (ref "RB3") (pin "1") (pinfunction "1_1") (pintype "passive"))
    )
    (net (code "143") (name "Net-(QB4-B)") (class "Default")
      (node (ref "QB4") (pin "1") (pinfunction "B_1") (pintype "passive"))
      (node (ref "RPW4") (pin "1") (pinfunction "1_1") (pintype "passive"))
    )
    (net (code "144") (name "Net-(QB4-C)") (class "Default")
      (node (ref "QB4") (pin "3") (pinfunction "C_3") (pintype "passive"))
      (node (ref "RA4") (pin "1") (pinfunction "1_1") (pintype "passive"))
      (node (ref "RB4") (pin "1") (pinfunction "1_1") (pintype "passive"))
    )
    (net (code "145") (name "Net-(QB5-B)") (class "Default")
      (node (ref "QB5") (pin "1") (pinfunction "B_1") (pintype "passive"))
      (node (ref "RPW5") (pin "1") (pinfunction "1_1") (pintype "passive"))
    )
    (net (code "146") (name "Net-(QB5-C)") (class "Default")
      (node (ref "QB5") (pin "3") (pinfunction "C_3") (pintype "passive"))
      (node (ref "RA5") (pin "1") (pinfunction "1_1") (pintype "passive"))
      (node (ref "RB5") (pin "1") (pinfunction "1_1") (pintype "passive"))
    )
    (net (code "147") (name "Net-(QB6-B)") (class "Default")
      (node (ref "QB6") (pin "1") (pinfunction "B_1") (pintype "passive"))
      (node (ref "RPW6") (pin "1") (pinfunction "1_1") (pintype "passive"))
    )
    (net (code "148") (name "Net-(QB6-C)") (class "Default")
      (node (ref "QB6") (pin "3") (pinfunction "C_3") (pintype "passive"))
      (node (ref "RA6") (pin "1") (pinfunction "1_1") (pintype "passive"))
      (node (ref "RB6") (pin "1") (pinfunction "1_1") (pintype "passive"))
    )
    (net (code "149") (name "Net-(QB7-B)") (class "Default")
      (node (ref "QB7") (pin "1") (pinfunction "B_1") (pintype "passive"))
      (node (ref "RPW7") (pin "1") (pinfunction "1_1") (pintype "passive"))
    )
    (net (code "150") (name "Net-(QB7-C)") (class "Default")
      (node (ref "QB7") (pin "3") (pinfunction "C_3") (pintype "passive"))
      (node (ref "RA7") (pin "1") (pinfunction "1_1") (pintype "passive"))
      (node (ref "RB7") (pin "1") (pinfunction "1_1") (pintype "passive"))
    )
    (net (code "151") (name "Net-(QB8-B)") (class "Default")
      (node (ref "QB8") (pin "1") (pinfunction "B_1") (pintype "passive"))
      (node (ref "RPW8") (pin "1") (pinfunction "1_1") (pintype "passive"))
    )
    (net (code "152") (name "Net-(QB8-C)") (class "Default")
      (node (ref "QB8") (pin "3") (pinfunction "C_3") (pintype "passive"))
      (node (ref "RA8") (pin "1") (pinfunction "1_1") (pintype "passive"))
      (node (ref "RB8") (pin "1") (pinfunction "1_1") (pintype "passive"))
    )
    (net (code "153") (name "Net-(QB9-B)") (class "Default")
      (node (ref "QB9") (pin "1") (pinfunction "B_1") (pintype "passive"))
      (node (ref "RPW9") (pin "1") (pinfunction "1_1") (pintype "passive"))
    )
    (net (code "154") (name "Net-(QB9-C)") (class "Default")
      (node (ref "QB9") (pin "3") (pinfunction "C_3") (pintype "passive"))
      (node (ref "RA9") (pin "1") (pinfunction "1_1") (pintype "passive"))
      (node (ref "RB9") (pin "1") (pinfunction "1_1") (pintype "passive"))
    )
    (net (code "155") (name "Net-(QB10-B)") (class "Default")
      (node (ref "QB10") (pin "1") (pinfunction "B_1") (pintype "passive"))
      (node (ref "RPW10") (pin "1") (pinfunction "1_1") (pintype "passive"))
    )
    (net (code "156") (name "Net-(QB10-C)") (class "Default")
      (node (ref "QB10") (pin "3") (pinfunction "C_3") (pintype "passive"))
      (node (ref "RA10") (pin "1") (pinfunction "1_1") (pintype "passive"))
      (node (ref "RB10") (pin "1") (pinfunction "1_1") (pintype "passive"))
    )
    (net (code "157") (name "Net-(QB11-B)") (class "Default")
      (node (ref "QB11") (pin "1") (pinfunction "B_1") (pintype "passive"))
      (node (ref "RPW11") (pin "1") (pinfunction "1_1") (pintype "passive"))
    )
    (net (code "158") (name "Net-(QB11-C)") (class "Default")
      (node (ref "QB11") (pin "3") (pinfunction "C_3") (pintype "passive"))
      (node (ref "RA11") (pin "1") (pinfunction "1_1") (pintype "passive"))
      (node (ref "RB11") (pin "1") (pinfunction "1_1") (pintype "passive"))
    )
    (net (code "159") (name "Net-(QB12-B)") (class "Default")
      (node (ref "QB12") (pin "1") (pinfunction "B_1") (pintype "passive"))
      (node (ref "RPW12") (pin "1") (pinfunction "1_1") (pintype "passive"))
    )
    (net (code "160") (name "Net-(QB12-C)") (class "Default")
      (node (ref "QB12") (pin "3") (pinfunction "C_3") (pintype "passive"))
      (node (ref "RA12") (pin "1") (pinfunction "1_1") (pintype "passive"))
      (node (ref "RB12") (pin "1") (pinfunction "1_1") (pintype "passive"))
    )
    (net (code "161") (name "Net-(R27-Pad2)") (class "Default")
      (node (ref "R27") (pin "2") (pinfunction "2_2") (pintype "passive"))
      (node (ref "RX3") (pin "A") (pinfunction "A_A") (pintype "passive"))
    )
    (net (code "162") (name "Net-(R28-Pad2)") (class "Default")
      (node (ref "R28") (pin "2") (pinfunction "2_2") (pintype "passive"))
      (node (ref "TX3") (pin "A") (pinfunction "A_A") (pintype "passive"))
    )
    (net (code "163") (name "Net-(U9-8-RP10{slash}PGED2{slash}EMCD2)") (class "Default")
      (node (ref "PIC_PROG") (pin "4") (pinfunction "4_4") (pintype "passive"))
      (node (ref "U9") (pin "8") (pinfunction "8-RP10/PGED2/EMCD2_8") (pintype "bidirectional"))
    )
    (net (code "164") (name "Net-(U9-9-RP11{slash}PGEC2)") (class "Default")
      (node (ref "LED_TOG") (pin "2") (pinfunction "2_2") (pintype "passive"))
      (node (ref "PIC_PROG") (pin "5") (pinfunction "5_5") (pintype "passive"))
      (node (ref "U9") (pin "9") (pinfunction "9-RP11/PGEC2_9") (pintype "bidirectional"))
    )
    (net (code "165") (name "Net-(U9-OSC1{slash}CLK1{slash}RA2-30)") (class "Default")
      (node (ref "C2") (pin "1") (pinfunction "1_1") (pintype "passive"))
      (node (ref "U9") (pin "30") (pinfunction "OSC1/CLK1/RA2-30_30") (pintype "bidirectional"))
      (node (ref "X1") (pin "1") (pinfunction "IN_1") (pintype "bidirectional"))
    )
    (net (code "166") (name "Net-(U9-OSC2{slash}CLK0{slash}RA3-31)") (class "Default")
      (node (ref "C4") (pin "1") (pinfunction "1_1") (pintype "passive"))
      (node (ref "U9") (pin "31") (pinfunction "OSC2/CLK0/RA3-31_31") (pintype "bidirectional"))
      (node (ref "X1") (pin "3") (pinfunction "OUT_3") (pintype "bidirectional"))
    )
    (net (code "167") (name "unconnected-(CN3-PadID)") (class "Default")
      (node (ref "CN3") (pin "ID") (pinfunction "ID_ID") (pintype "bidirectional"))
    )
    (net (code "168") (name "unconnected-(IC2-(A8)PC0-Pad53)") (class "Default")
      (node (ref "IC2") (pin "53") (pinfunction "(A8)PC0_53") (pintype "bidirectional"))
    )
    (net (code "169") (name "unconnected-(IC2-(A9)PC1-Pad54)") (class "Default")
      (node (ref "IC2") (pin "54") (pinfunction "(A9)PC1_54") (pintype "bidirectional"))
    )
    (net (code "170") (name "unconnected-(IC2-(A10)PC2-Pad55)") (class "Default")
      (node (ref "IC2") (pin "55") (pinfunction "(A10)PC2_55") (pintype "bidirectional"))
    )
    (net (code "171") (name "unconnected-(IC2-(A11)PC3-Pad56)") (class "Default")
      (node (ref "IC2") (pin "56") (pinfunction "(A11)PC3_56") (pintype "bidirectional"))
    )
    (net (code "172") (name "unconnected-(IC2-(A12)PC4-Pad57)") (class "Default")
      (node (ref "IC2") (pin "57") (pinfunction "(A12)PC4_57") (pintype "bidirectional"))
    )
    (net (code "173") (name "unconnected-(IC2-(A13)PC5-Pad58)") (class "Default")
      (node (ref "IC2") (pin "58") (pinfunction "(A13)PC5_58") (pintype "bidirectional"))
    )
    (net (code "174") (name "unconnected-(IC2-(A14)PC6-Pad59)") (class "Default")
      (node (ref "IC2") (pin "59") (pinfunction "(A14)PC6_59") (pintype "bidirectional"))
    )
    (net (code "175") (name "unconnected-(IC2-(A15)PC7-Pad60)") (class "Default")
      (node (ref "IC2") (pin "60") (pinfunction "(A15)PC7_60") (pintype "bidirectional"))
    )
    (net (code "176") (name "unconnected-(IC2-(AD0)PA0-Pad78)") (class "Default")
      (node (ref "IC2") (pin "78") (pinfunction "(AD0)PA0_78") (pintype "bidirectional"))
    )
    (net (code "177") (name "unconnected-(IC2-(AD1)PA1-Pad77)") (class "Default")
      (node (ref "IC2") (pin "77") (pinfunction "(AD1)PA1_77") (pintype "bidirectional"))
    )
    (net (code "178") (name "unconnected-(IC2-(AD2)PA2-Pad76)") (class "Default")
      (node (ref "IC2") (pin "76") (pinfunction "(AD2)PA2_76") (pintype "bidirectional"))
    )
    (net (code "179") (name "unconnected-(IC2-(AD3)PA3-Pad75)") (class "Default")
      (node (ref "IC2") (pin "75") (pinfunction "(AD3)PA3_75") (pintype "bidirectional"))
    )
    (net (code "180") (name "unconnected-(IC2-(AD4)PA4-Pad74)") (class "Default")
      (node (ref "IC2") (pin "74") (pinfunction "(AD4)PA4_74") (pintype "bidirectional"))
    )
    (net (code "181") (name "unconnected-(IC2-(AD5)PA5-Pad73)") (class "Default")
      (node (ref "IC2") (pin "73") (pinfunction "(AD5)PA5_73") (pintype "bidirectional"))
    )
    (net (code "182") (name "unconnected-(IC2-(AD6)PA6-Pad72)") (class "Default")
      (node (ref "IC2") (pin "72") (pinfunction "(AD6)PA6_72") (pintype "bidirectional"))
    )
    (net (code "183") (name "unconnected-(IC2-(AD7)PA7-Pad71)") (class "Default")
      (node (ref "IC2") (pin "71") (pinfunction "(AD7)PA7_71") (pintype "bidirectional"))
    )
    (net (code "184") (name "unconnected-(IC2-(ADC0)PF0-Pad97)") (class "Default")
      (node (ref "IC2") (pin "97") (pinfunction "(ADC0)PF0_97") (pintype "bidirectional"))
    )
    (net (code "185") (name "unconnected-(IC2-(ADC1)PF1-Pad96)") (class "Default")
      (node (ref "IC2") (pin "96") (pinfunction "(ADC1)PF1_96") (pintype "bidirectional"))
    )
    (net (code "186") (name "unconnected-(IC2-(ADC2)PF2-Pad95)") (class "Default")
      (node (ref "IC2") (pin "95") (pinfunction "(ADC2)PF2_95") (pintype "bidirectional"))
    )
    (net (code "187") (name "unconnected-(IC2-(ADC3)PF3-Pad94)") (class "Default")
      (node (ref "IC2") (pin "94") (pinfunction "(ADC3)PF3_94") (pintype "bidirectional"))
    )
    (net (code "188") (name "unconnected-(IC2-(ADC4{slash}TCK)PF4-Pad93)") (class "Default")
      (node (ref "IC2") (pin "93") (pinfunction "(ADC4/TCK)PF4_93") (pintype "bidirectional"))
    )
    (net (code "189") (name "unconnected-(IC2-(ADC5{slash}TMS)PF5-Pad92)") (class "Default")
      (node (ref "IC2") (pin "92") (pinfunction "(ADC5/TMS)PF5_92") (pintype "bidirectional"))
    )
    (net (code "190") (name "unconnected-(IC2-(ADC6{slash}TDO)PF6-Pad91)") (class "Default")
      (node (ref "IC2") (pin "91") (pinfunction "(ADC6/TDO)PF6_91") (pintype "bidirectional"))
    )
    (net (code "191") (name "unconnected-(IC2-(ADC7{slash}TDI)PF7-Pad90)") (class "Default")
      (node (ref "IC2") (pin "90") (pinfunction "(ADC7/TDI)PF7_90") (pintype "bidirectional"))
    )
    (net (code "192") (name "unconnected-(IC2-(ALE)PG2-Pad70)") (class "Default")
      (node (ref "IC2") (pin "70") (pinfunction "(ALE)PG2_70") (pintype "bidirectional"))
    )
    (net (code "193") (name "unconnected-(IC2-(CLKO{slash}ICP3{slash}INT7)PE7-Pad9)") (class "Default")
      (node (ref "IC2") (pin "9") (pinfunction "(CLKO/ICP3/INT7)PE7_9") (pintype "bidirectional"))
    )
    (net (code "194") (name "unconnected-(IC2-(ICP1)PD4-Pad47)") (class "Default")
      (node (ref "IC2") (pin "47") (pinfunction "(ICP1)PD4_47") (pintype "bidirectional"))
    )
    (net (code "195") (name "unconnected-(IC2-(OC0B)PG5-Pad1)") (class "Default")
      (node (ref "IC2") (pin "1") (pinfunction "(OC0B)PG5_1") (pintype "bidirectional"))
    )
    (net (code "196") (name "unconnected-(IC2-(RD)PG1-Pad52)") (class "Default")
      (node (ref "IC2") (pin "52") (pinfunction "(RD)PG1_52") (pintype "bidirectional"))
    )
    (net (code "197") (name "unconnected-(IC2-(SS{slash}PCINT0)PB0-Pad19)") (class "Default")
      (node (ref "IC2") (pin "19") (pinfunction "(SS/PCINT0)PB0_19") (pintype "bidirectional"))
    )
    (net (code "198") (name "unconnected-(IC2-(T0)PD7-Pad50)") (class "Default")
      (node (ref "IC2") (pin "50") (pinfunction "(T0)PD7_50") (pintype "bidirectional"))
    )
    (net (code "199") (name "unconnected-(IC2-(T1)PD6-Pad49)") (class "Default")
      (node (ref "IC2") (pin "49") (pinfunction "(T1)PD6_49") (pintype "bidirectional"))
    )
    (net (code "200") (name "unconnected-(IC2-(T3{slash}INT6)PE6-Pad8)") (class "Default")
      (node (ref "IC2") (pin "8") (pinfunction "(T3/INT6)PE6_8") (pintype "bidirectional"))
    )
    (net (code "201") (name "unconnected-(IC2-(TOSC1)PG4-Pad29)") (class "Default")
      (node (ref "IC2") (pin "29") (pinfunction "(TOSC1)PG4_29") (pintype "bidirectional"))
    )
    (net (code "202") (name "unconnected-(IC2-(TOSC2)PG3-Pad28)") (class "Default")
      (node (ref "IC2") (pin "28") (pinfunction "(TOSC2)PG3_28") (pintype "bidirectional"))
    )
    (net (code "203") (name "unconnected-(IC2-(WR)PG0-Pad51)") (class "Default")
      (node (ref "IC2") (pin "51") (pinfunction "(WR)PG0_51") (pintype "bidirectional"))
    )
    (net (code "204") (name "unconnected-(IC2-(XCK0{slash}AIN0)PE2-Pad4)") (class "Default")
      (node (ref "IC2") (pin "4") (pinfunction "(XCK0/AIN0)PE2_4") (pintype "bidirectional"))
    )
    (net (code "205") (name "unconnected-(IC2-(XCK1)PD5-Pad48)") (class "Default")
      (node (ref "IC2") (pin "48") (pinfunction "(XCK1)PD5_48") (pintype "bidirectional"))
    )
    (net (code "206") (name "unconnected-(IC2-AREF-Pad98)") (class "Default")
      (node (ref "IC2") (pin "98") (pinfunction "AREF_98") (pintype "bidirectional"))
    )
    (net (code "207") (name "unconnected-(IC2-PH3(OC4A)-Pad15)") (class "Default")
      (node (ref "IC2") (pin "15") (pinfunction "PH3(OC4A)_15") (pintype "bidirectional"))
    )
    (net (code "208") (name "unconnected-(IC2-PH4(OC4B)-Pad16)") (class "Default")
      (node (ref "IC2") (pin "16") (pinfunction "PH4(OC4B)_16") (pintype "bidirectional"))
    )
    (net (code "209") (name "unconnected-(IC2-PH5(OC4C)-Pad17)") (class "Default")
      (node (ref "IC2") (pin "17") (pinfunction "PH5(OC4C)_17") (pintype "bidirectional"))
    )
    (net (code "210") (name "unconnected-(IC2-PH6(OC2B)-Pad18)") (class "Default")
      (node (ref "IC2") (pin "18") (pinfunction "PH6(OC2B)_18") (pintype "bidirectional"))
    )
    (net (code "211") (name "unconnected-(IC2-PH7(T4)-Pad27)") (class "Default")
      (node (ref "IC2") (pin "27") (pinfunction "PH7(T4)_27") (pintype "bidirectional"))
    )
    (net (code "212") (name "unconnected-(IC2-PJ2(XCK3{slash}PCINT11)-Pad65)") (class "Default")
      (node (ref "IC2") (pin "65") (pinfunction "PJ2(XCK3/PCINT11)_65") (pintype "bidirectional"))
    )
    (net (code "213") (name "unconnected-(IC2-PJ3(PCINT12)-Pad66)") (class "Default")
      (node (ref "IC2") (pin "66") (pinfunction "PJ3(PCINT12)_66") (pintype "bidirectional"))
    )
    (net (code "214") (name "unconnected-(IC2-PJ4(PCINT13)-Pad67)") (class "Default")
      (node (ref "IC2") (pin "67") (pinfunction "PJ4(PCINT13)_67") (pintype "bidirectional"))
    )
    (net (code "215") (name "unconnected-(IC2-PJ5(PCINT14)-Pad68)") (class "Default")
      (node (ref "IC2") (pin "68") (pinfunction "PJ5(PCINT14)_68") (pintype "bidirectional"))
    )
    (net (code "216") (name "unconnected-(IC2-PJ6(PCINT15)-Pad69)") (class "Default")
      (node (ref "IC2") (pin "69") (pinfunction "PJ6(PCINT15)_69") (pintype "bidirectional"))
    )
    (net (code "217") (name "unconnected-(IC2-PJ7-Pad79)") (class "Default")
      (node (ref "IC2") (pin "79") (pinfunction "PJ7_79") (pintype "bidirectional"))
    )
    (net (code "218") (name "unconnected-(IC2-PK7(ADC15{slash}PCINT23)-Pad82)") (class "Default")
      (node (ref "IC2") (pin "82") (pinfunction "PK7(ADC15/PCINT23)_82") (pintype "bidirectional"))
    )
    (net (code "219") (name "unconnected-(IC2-PL6-Pad41)") (class "Default")
      (node (ref "IC2") (pin "41") (pinfunction "PL6_41") (pintype "bidirectional"))
    )
    (net (code "220") (name "unconnected-(IC2-PL7-Pad42)") (class "Default")
      (node (ref "IC2") (pin "42") (pinfunction "PL7_42") (pintype "bidirectional"))
    )
    (net (code "221") (name "unconnected-(IC4-CBUS2-Pad13)") (class "Default")
      (node (ref "IC4") (pin "13") (pinfunction "CBUS2_13") (pintype "input"))
    )
    (net (code "222") (name "unconnected-(IC4-CBUS3-Pad14)") (class "Default")
      (node (ref "IC4") (pin "14") (pinfunction "CBUS3_14") (pintype "input"))
    )
    (net (code "223") (name "unconnected-(IC4-CBUS4-Pad12)") (class "Default")
      (node (ref "IC4") (pin "12") (pinfunction "CBUS4_12") (pintype "input"))
    )
    (net (code "224") (name "unconnected-(IC4-OSCI-Pad27)") (class "Default")
      (node (ref "IC4") (pin "27") (pinfunction "OSCI_27") (pintype "input"))
    )
    (net (code "225") (name "unconnected-(IC4-OSCO-Pad28)") (class "Default")
      (node (ref "IC4") (pin "28") (pinfunction "OSCO_28") (pintype "input"))
    )
    (net (code "226") (name "unconnected-(IC4-~{CTS}-Pad11)") (class "Default")
      (node (ref "IC4") (pin "11") (pinfunction "~{CTS}_11") (pintype "input"))
    )
    (net (code "227") (name "unconnected-(IC4-~{DCD}-Pad10)") (class "Default")
      (node (ref "IC4") (pin "10") (pinfunction "~{DCD}_10") (pintype "input"))
    )
    (net (code "228") (name "unconnected-(IC4-~{DSR}-Pad9)") (class "Default")
      (node (ref "IC4") (pin "9") (pinfunction "~{DSR}_9") (pintype "input"))
    )
    (net (code "229") (name "unconnected-(IC4-~{DTR}-Pad2)") (class "Default")
      (node (ref "IC4") (pin "2") (pinfunction "~{DTR}_2") (pintype "input"))
    )
    (net (code "230") (name "unconnected-(IC4-~{RESET}-Pad19)") (class "Default")
      (node (ref "IC4") (pin "19") (pinfunction "~{RESET}_19") (pintype "input"))
    )
    (net (code "231") (name "unconnected-(IC4-~{RI}-Pad6)") (class "Default")
      (node (ref "IC4") (pin "6") (pinfunction "~{RI}_6") (pintype "input"))
    )
    (net (code "232") (name "unconnected-(IC4-~{RTS}-Pad3)") (class "Default")
      (node (ref "IC4") (pin "3") (pinfunction "~{RTS}_3") (pintype "input"))
    )
    (net (code "233") (name "unconnected-(JP7-Pad1)") (class "Default")
      (node (ref "JP7") (pin "1") (pinfunction "1_1") (pintype "passive"))
    )
    (net (code "234") (name "unconnected-(OPTO1-E-Pad3)") (class "Default")
      (node (ref "OPTO1") (pin "3") (pinfunction "E_3") (pintype "bidirectional"))
    )
    (net (code "235") (name "unconnected-(S2-P-Pad3)") (class "Default")
      (node (ref "S2") (pin "3") (pinfunction "P_3") (pintype "passive"))
    )
    (net (code "236") (name "unconnected-(S2-S-Pad1)") (class "Default")
      (node (ref "S2") (pin "1") (pinfunction "S_1") (pintype "passive"))
    )
    (net (code "237") (name "unconnected-(U9-PGED3{slash}ASDA1{slash}RB5-41-Pad41)") (class "Default")
      (node (ref "U9") (pin "41") (pinfunction "PGED3/ASDA1/RB5-41_41") (pintype "bidirectional"))
    )
  )
)
